# io-board-e-4.net
KiCad netlist of a schematic drawn in EAGLE
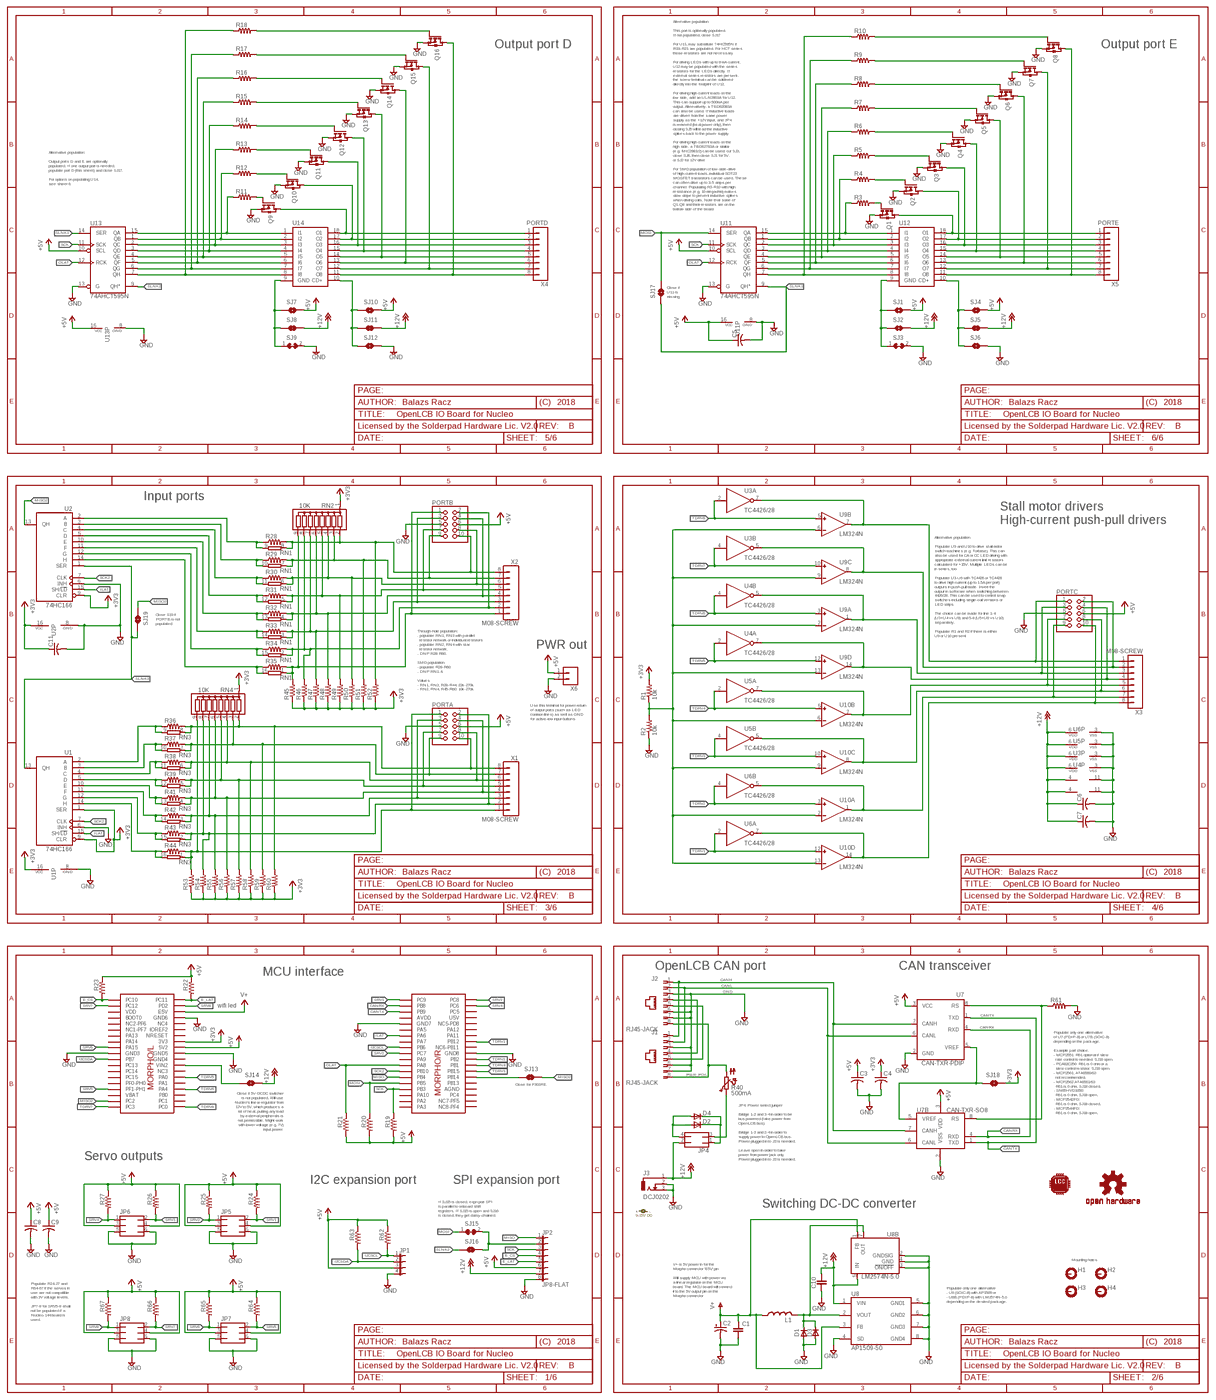
[diagram p0: schematic, sheet 1, overview]
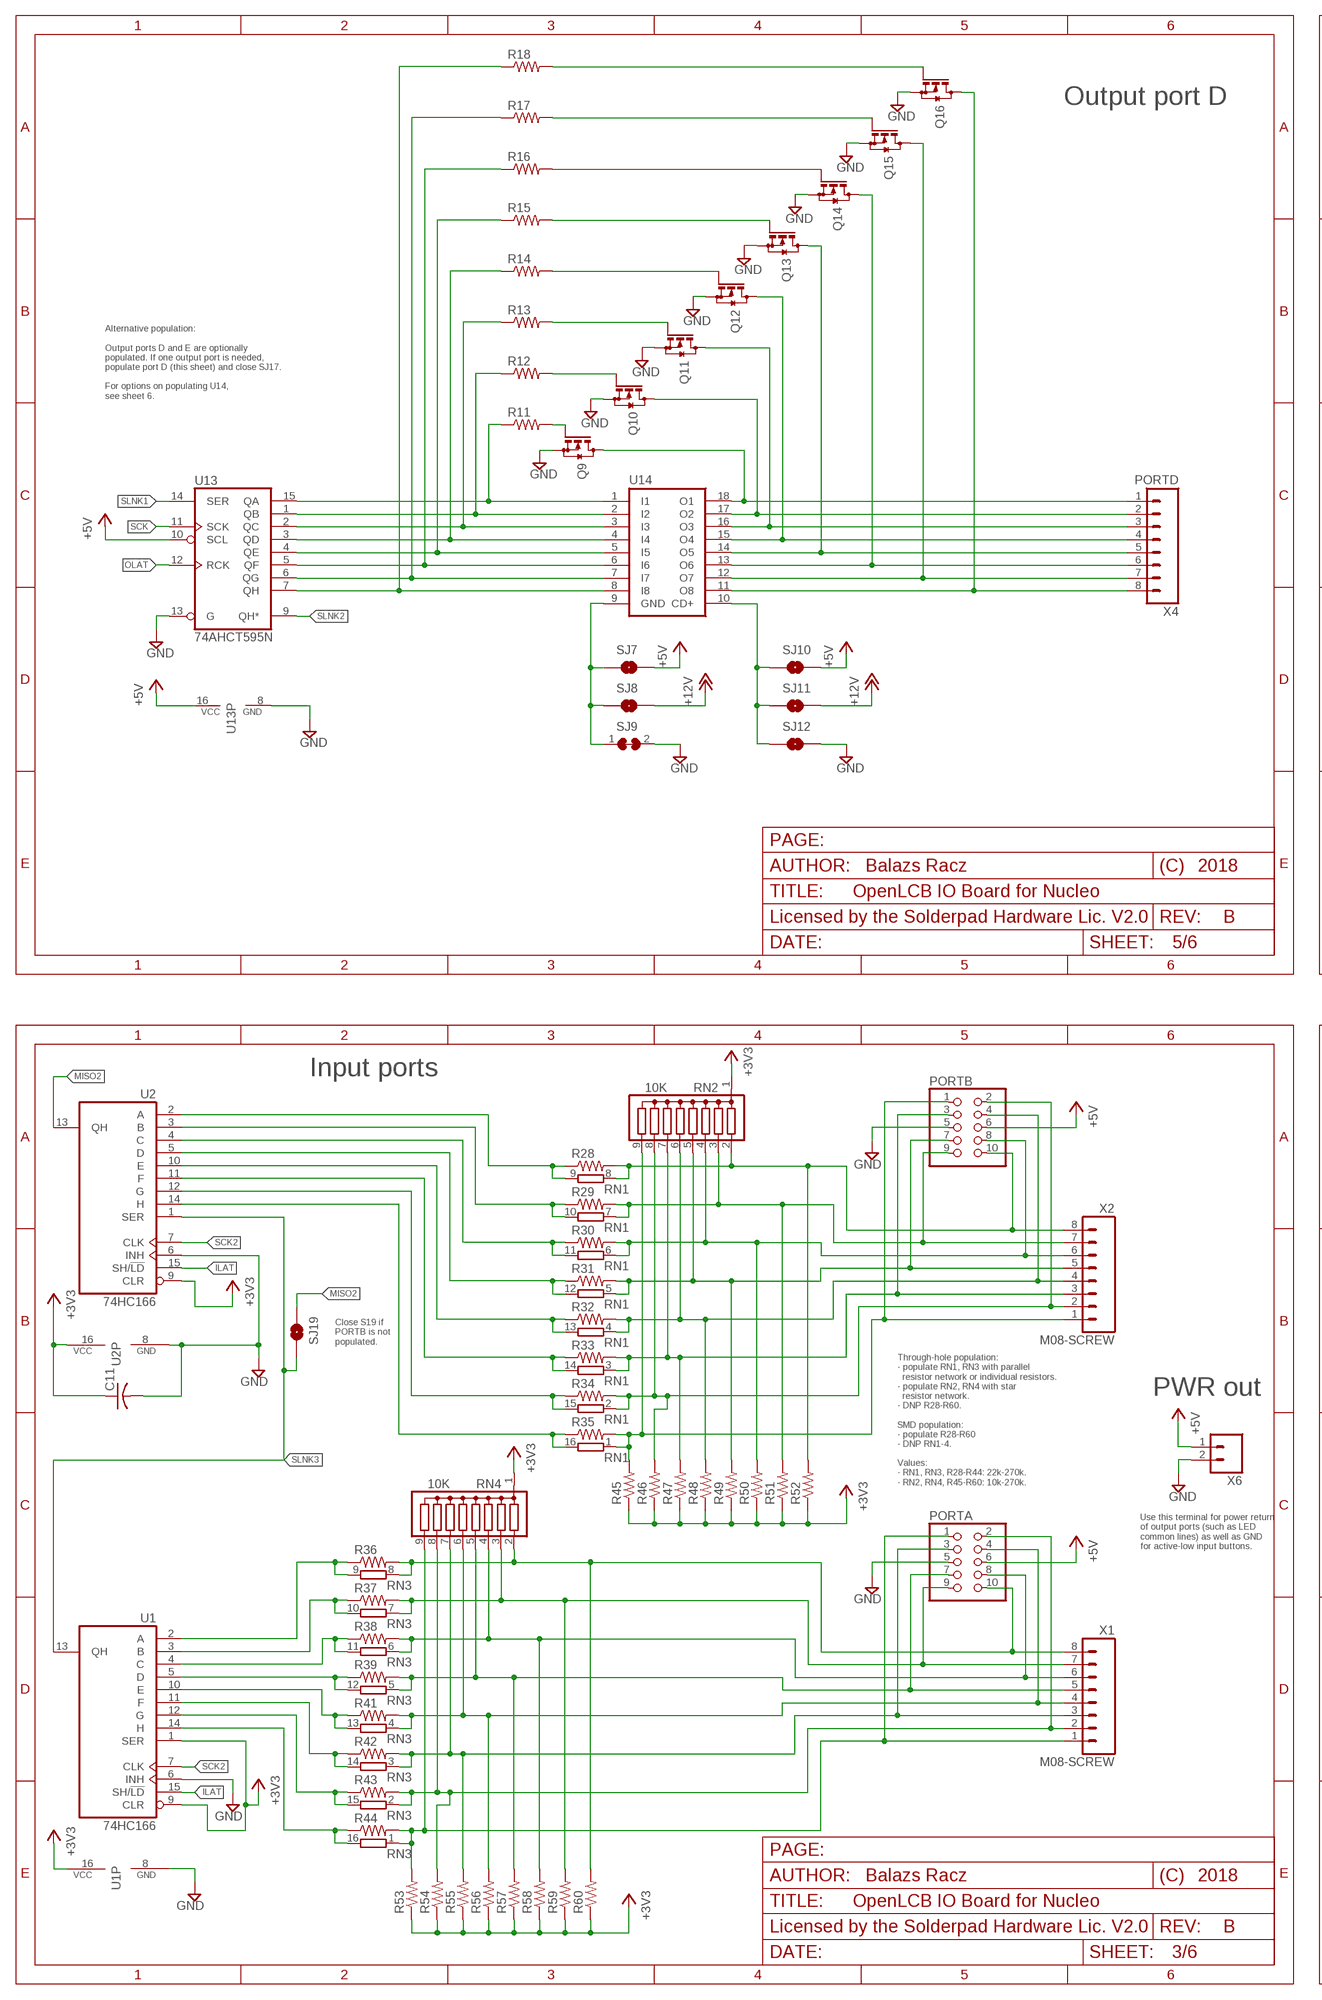
[diagram p1: schematic, sheet 1, part 1 of 4]
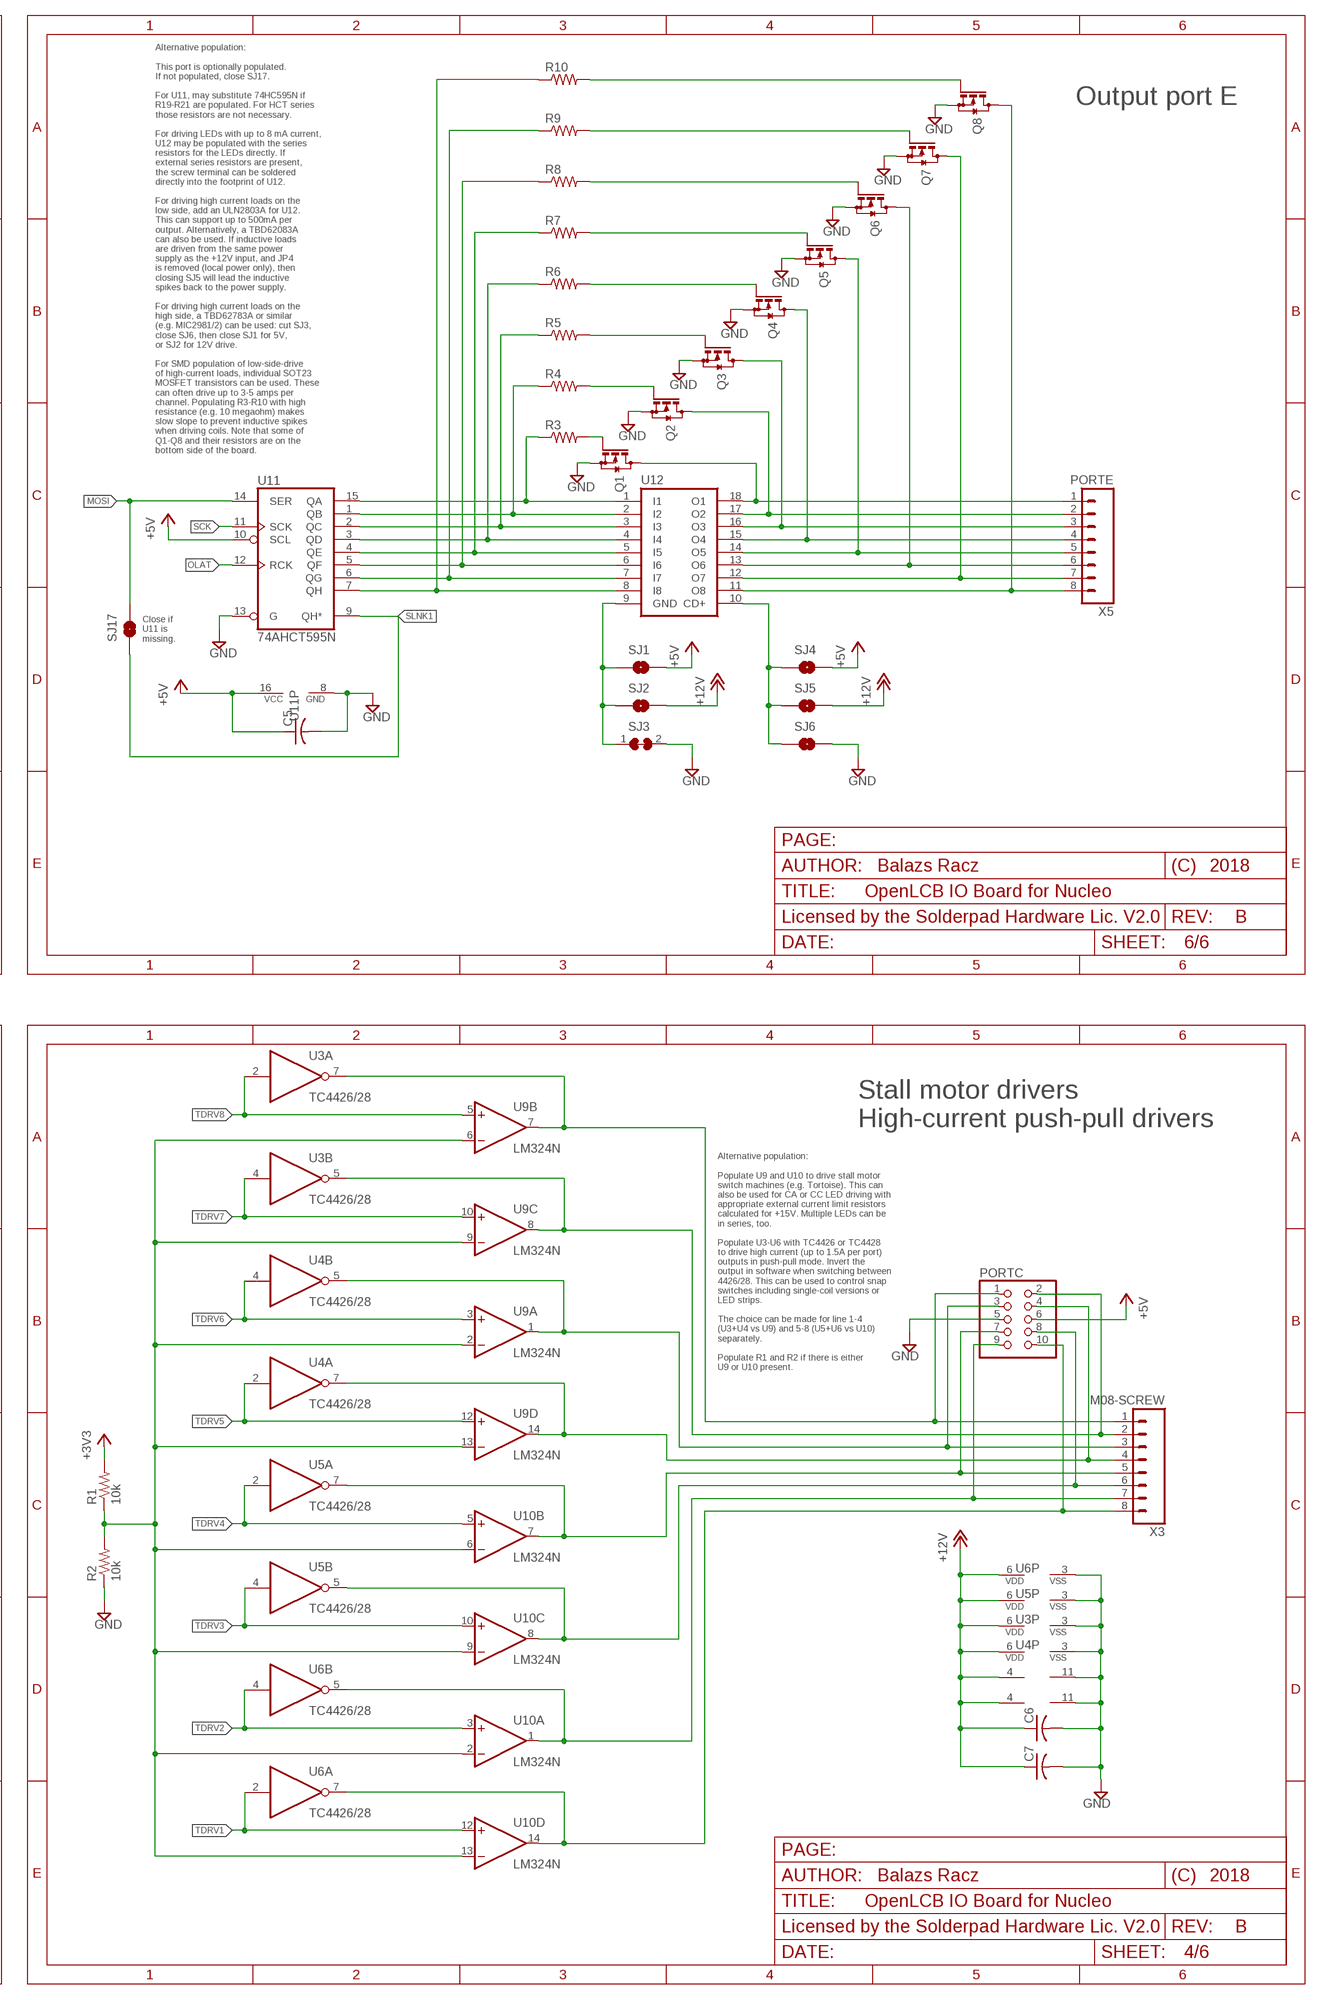
[diagram p2: schematic, sheet 1, part 2 of 4]
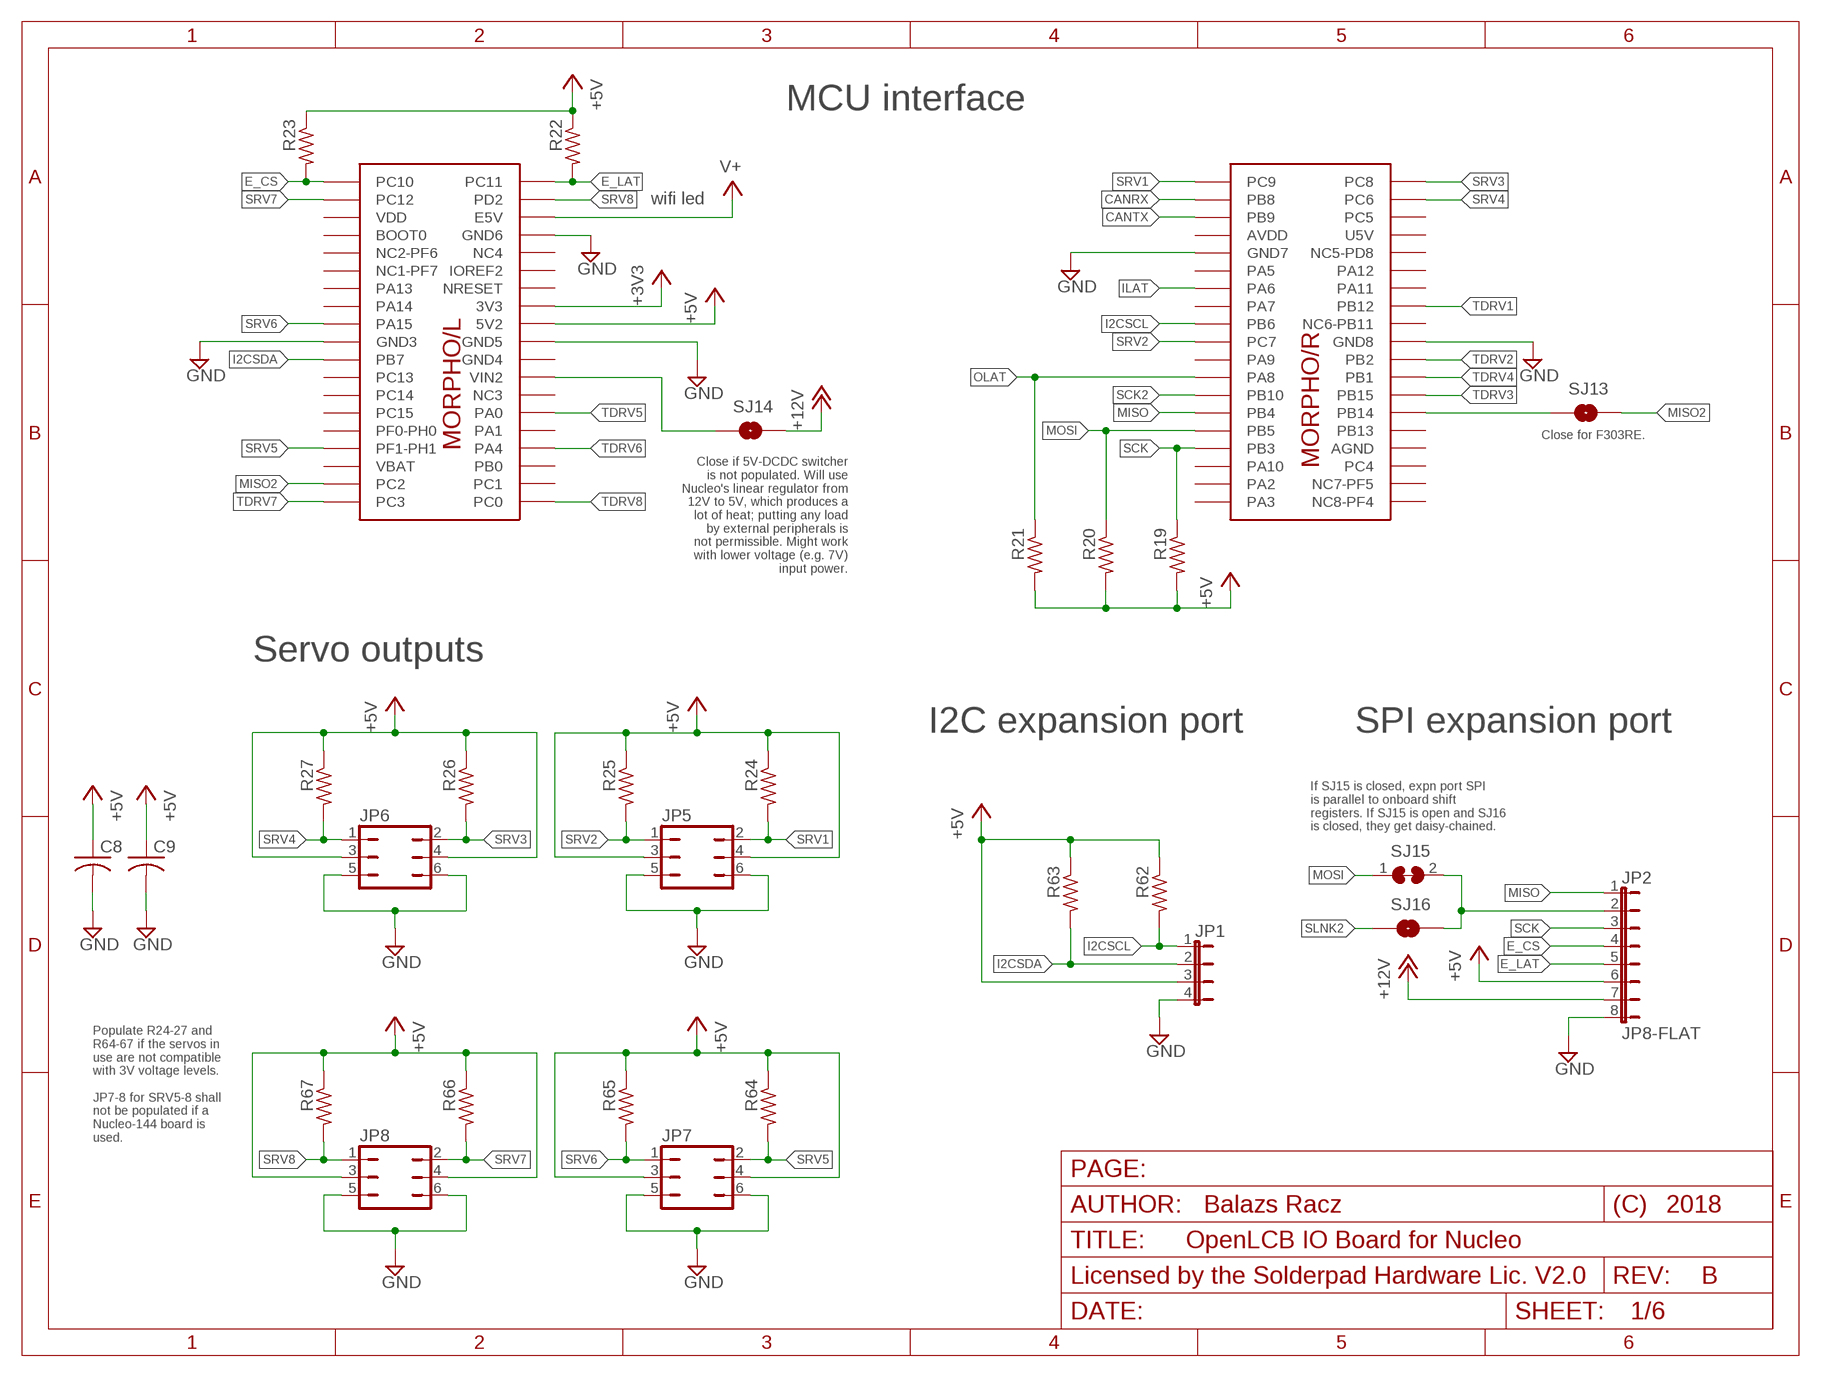
[diagram p3: schematic, sheet 1, part 3 of 4]
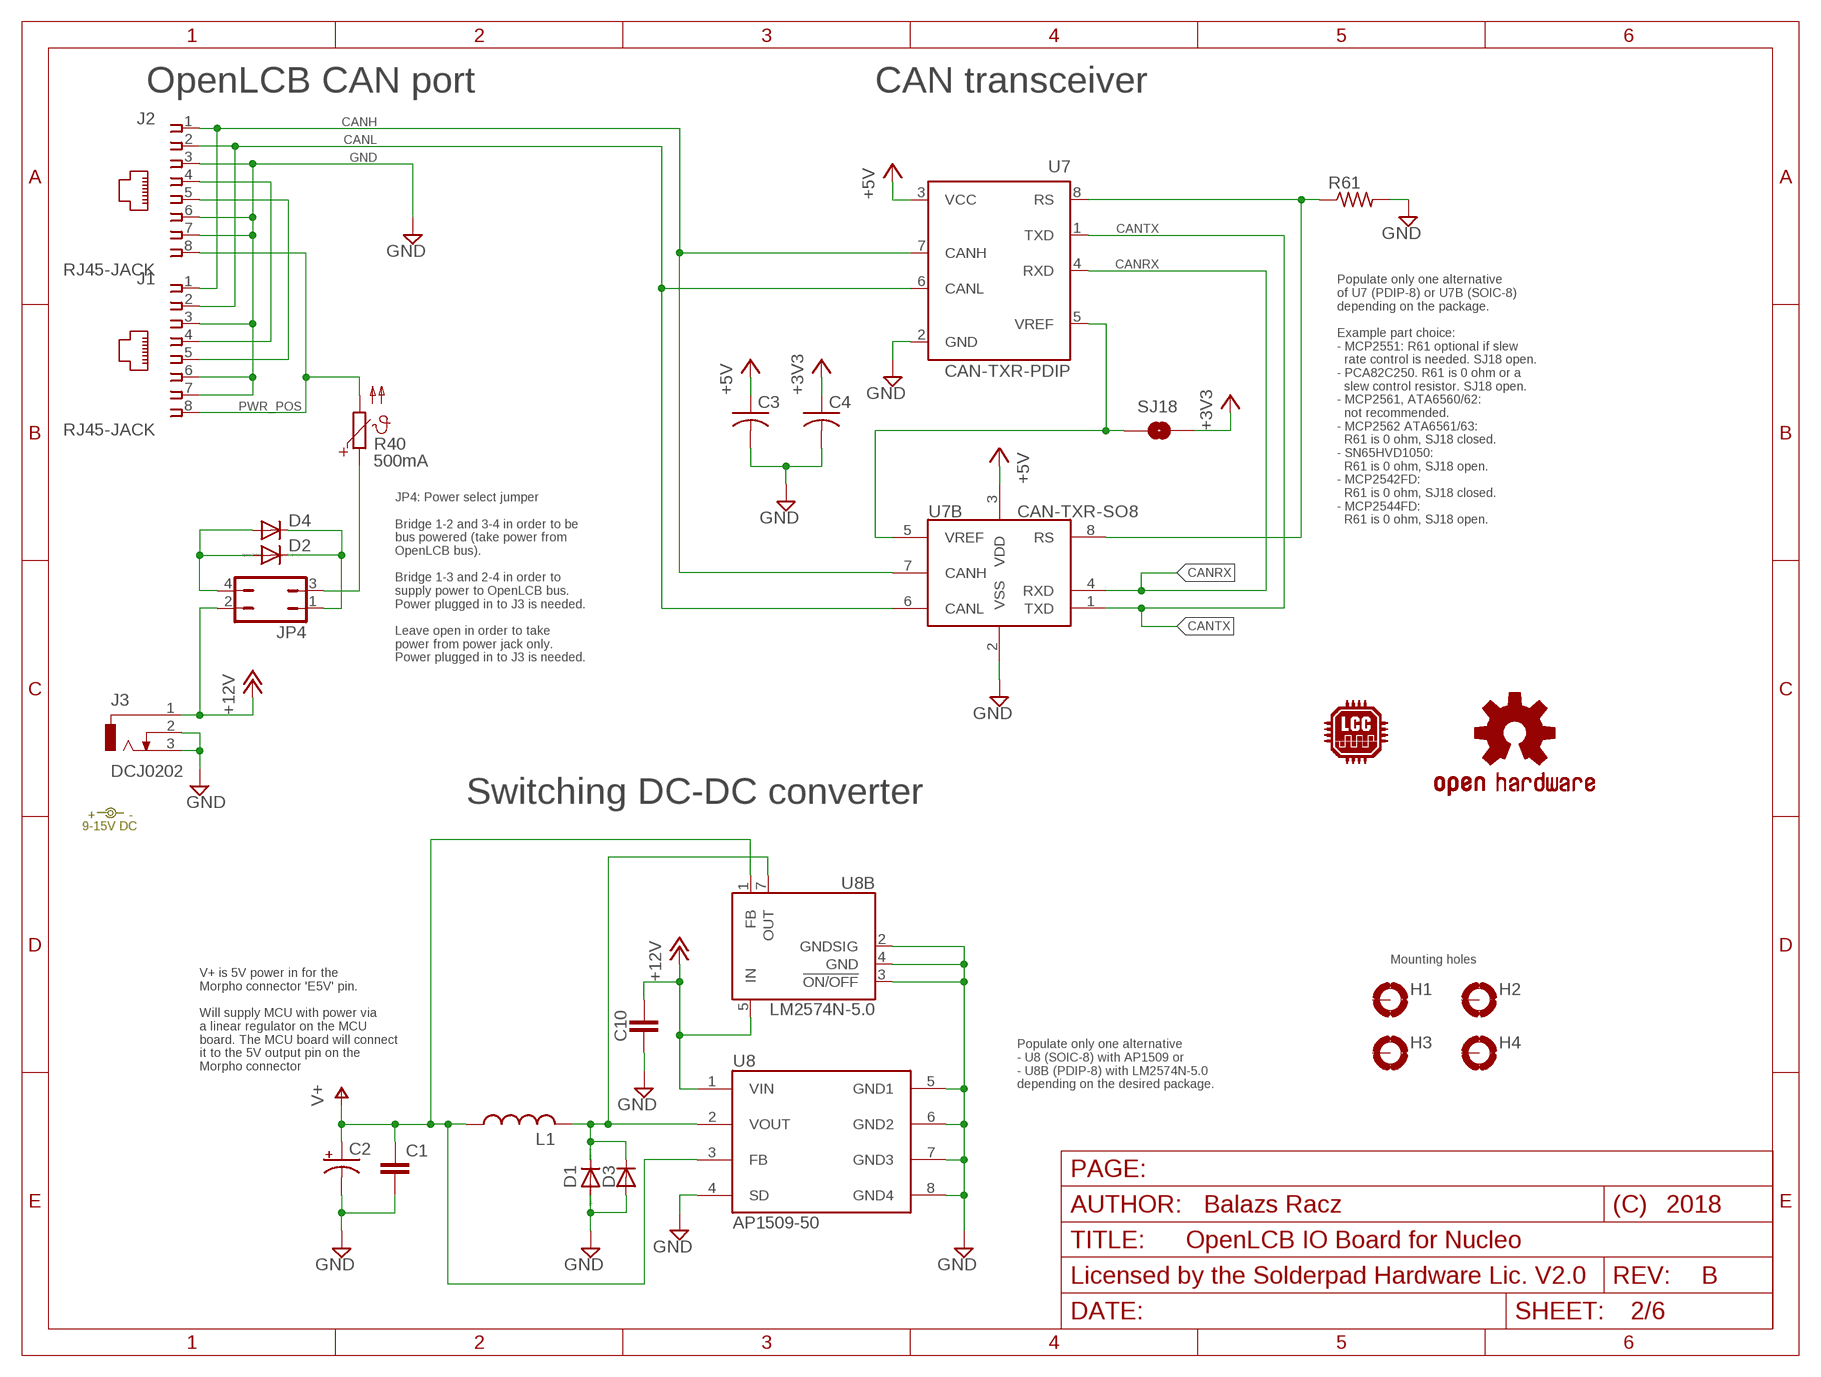
[diagram p4: schematic, sheet 1, part 4 of 4]

(export (version "E")
  (design (tool "Eeschema 10.0.6"))
  (components
    (comp (ref "+12V")
      (value "9-15V DC")
      (footprint "eagle-import:POWER_USAGE")
      (libsource (lib "eagle-import") (part "DOC-POWER_LABEL"))
    )
    (comp (ref "C1")
      (value "C-EUC1206")
      (footprint "eagle-import:C1206")
      (libsource (lib "eagle-import") (part "C-EUC1206"))
    )
    (comp (ref "C2")
      (value "CPOL-USE2.5-5")
      (footprint "eagle-import:E2,5-5")
      (libsource (lib "eagle-import") (part "CPOL-USE2.5-5"))
    )
    (comp (ref "C3")
      (value "C-USC0805")
      (footprint "eagle-import:C0805")
      (libsource (lib "eagle-import") (part "C-USC0805"))
    )
    (comp (ref "C4")
      (value "C-USC0805")
      (footprint "eagle-import:C0805")
      (libsource (lib "eagle-import") (part "C-USC0805"))
    )
    (comp (ref "C5")
      (value "C-USC0805")
      (footprint "eagle-import:C0805")
      (libsource (lib "eagle-import") (part "C-USC0805"))
    )
    (comp (ref "C6")
      (value "C-USC1206")
      (footprint "eagle-import:C1206")
      (libsource (lib "eagle-import") (part "C-USC1206"))
    )
    (comp (ref "C7")
      (value "C-USC1206")
      (footprint "eagle-import:C1206")
      (libsource (lib "eagle-import") (part "C-USC1206"))
    )
    (comp (ref "C8")
      (value "C-USC1206")
      (footprint "eagle-import:C1206")
      (libsource (lib "eagle-import") (part "C-USC1206"))
    )
    (comp (ref "C9")
      (value "C-USC1206")
      (footprint "eagle-import:C1206")
      (libsource (lib "eagle-import") (part "C-USC1206"))
    )
    (comp (ref "C10")
      (value "C-EUC1206")
      (footprint "eagle-import:C1206")
      (libsource (lib "eagle-import") (part "C-EUC1206"))
    )
    (comp (ref "C11")
      (value "C-USC0805")
      (footprint "eagle-import:C0805")
      (libsource (lib "eagle-import") (part "C-USC0805"))
    )
    (comp (ref "D1")
      (value "DIODE-DO41-7.6")
      (footprint "eagle-import:DO41-7.6")
      (libsource (lib "eagle-import") (part "DIODE-DO41-7.6"))
    )
    (comp (ref "D2")
      (value "DIODE-DO41-7.6")
      (footprint "eagle-import:DO41-7.6")
      (libsource (lib "eagle-import") (part "DIODE-DO41-7.6"))
    )
    (comp (ref "D3")
      (value "DIODEDO-214AA-NODOC")
      (footprint "eagle-import:DO214AA-NODOC")
      (libsource (lib "eagle-import") (part "DIODEDO-214AA-NODOC"))
    )
    (comp (ref "D4")
      (value "DIODEDO-214AA-NODOC")
      (footprint "eagle-import:DO214AA-NODOC")
      (libsource (lib "eagle-import") (part "DIODEDO-214AA-NODOC"))
    )
    (comp (ref "H1")
      (value "MOUNT-PAD-ROUND3.3")
      (footprint "eagle-import:3,3-PAD")
      (libsource (lib "eagle-import") (part "MOUNT-PAD-ROUND3.3"))
    )
    (comp (ref "H2")
      (value "MOUNT-PAD-ROUND3.3")
      (footprint "eagle-import:3,3-PAD")
      (libsource (lib "eagle-import") (part "MOUNT-PAD-ROUND3.3"))
    )
    (comp (ref "H3")
      (value "MOUNT-PAD-ROUND3.3")
      (footprint "eagle-import:3,3-PAD")
      (libsource (lib "eagle-import") (part "MOUNT-PAD-ROUND3.3"))
    )
    (comp (ref "H4")
      (value "MOUNT-PAD-ROUND3.3")
      (footprint "eagle-import:3,3-PAD")
      (libsource (lib "eagle-import") (part "MOUNT-PAD-ROUND3.3"))
    )
    (comp (ref "J1")
      (value "RJ45-JACK")
      (footprint "eagle-import:RJ45-PULSE-E5J88")
      (libsource (lib "eagle-import") (part "RJ45-JACKRJ45-PULSE-E5J00"))
    )
    (comp (ref "J2")
      (value "RJ45-JACK")
      (footprint "eagle-import:RJ45-PULSE-E5J88")
      (libsource (lib "eagle-import") (part "RJ45-JACKRJ45-PULSE-E5J00"))
    )
    (comp (ref "J3")
      (value "DCJ0202")
      (footprint "eagle-import:DCJ0202")
      (libsource (lib "eagle-import") (part "DCJ0202"))
    )
    (comp (ref "JP1")
      (value "JP4-FLAT")
      (footprint "eagle-import:JP4F")
      (libsource (lib "eagle-import") (part "JP4-FLAT"))
    )
    (comp (ref "JP2")
      (value "JP8-FLAT")
      (footprint "eagle-import:JP8F")
      (libsource (lib "eagle-import") (part "JP8-FLAT"))
    )
    (comp (ref "JP4")
      (value "JP2Q")
      (footprint "eagle-import:JP2Q")
      (libsource (lib "eagle-import") (part "JP2Q"))
    )
    (comp (ref "JP5")
      (value "JP3Q")
      (footprint "eagle-import:JP3Q")
      (libsource (lib "eagle-import") (part "JP3Q"))
    )
    (comp (ref "JP6")
      (value "JP3Q")
      (footprint "eagle-import:JP3Q")
      (libsource (lib "eagle-import") (part "JP3Q"))
    )
    (comp (ref "JP7")
      (value "JP3Q")
      (footprint "eagle-import:JP3Q")
      (libsource (lib "eagle-import") (part "JP3Q"))
    )
    (comp (ref "JP8")
      (value "JP3Q")
      (footprint "eagle-import:JP3Q")
      (libsource (lib "eagle-import") (part "JP3Q"))
    )
    (comp (ref "L1")
      (value "L-US")
      (footprint "eagle-import:L5-8,5")
      (libsource (lib "eagle-import") (part "L-US"))
    )
    (comp (ref "LG1")
      (value "LCC_LOGO")
      (footprint "eagle-import:LCC_LOGO")
      (libsource (lib "eagle-import") (part "LCC_LOGO"))
    )
    (comp (ref "LOGO1")
      (value "DOC-OSHW-LOGOM")
      (footprint "eagle-import:OSHW-LOGO-M")
      (libsource (lib "eagle-import") (part "DOC-OSHW-LOGOM"))
    )
    (comp (ref "PORTA")
      (value "PINHD-2X5CN")
      (footprint "eagle-import:CON10M")
      (libsource (lib "eagle-import") (part "PINHD-2X5CN"))
    )
    (comp (ref "PORTB")
      (value "PINHD-2X5CN")
      (footprint "eagle-import:CON10M")
      (libsource (lib "eagle-import") (part "PINHD-2X5CN"))
    )
    (comp (ref "PORTC")
      (value "PINHD-2X5CN")
      (footprint "eagle-import:CON10M")
      (libsource (lib "eagle-import") (part "PINHD-2X5CN"))
    )
    (comp (ref "Q1")
      (value "BSS123")
      (footprint "eagle-import:SOT23")
      (libsource (lib "eagle-import") (part "BSS123"))
    )
    (comp (ref "Q2")
      (value "BSS123")
      (footprint "eagle-import:SOT23")
      (libsource (lib "eagle-import") (part "BSS123"))
    )
    (comp (ref "Q3")
      (value "BSS123")
      (footprint "eagle-import:SOT23")
      (libsource (lib "eagle-import") (part "BSS123"))
    )
    (comp (ref "Q4")
      (value "BSS123")
      (footprint "eagle-import:SOT23")
      (libsource (lib "eagle-import") (part "BSS123"))
    )
    (comp (ref "Q5")
      (value "BSS123")
      (footprint "eagle-import:SOT23")
      (libsource (lib "eagle-import") (part "BSS123"))
    )
    (comp (ref "Q6")
      (value "BSS123")
      (footprint "eagle-import:SOT23")
      (libsource (lib "eagle-import") (part "BSS123"))
    )
    (comp (ref "Q7")
      (value "BSS123")
      (footprint "eagle-import:SOT23")
      (libsource (lib "eagle-import") (part "BSS123"))
    )
    (comp (ref "Q8")
      (value "BSS123")
      (footprint "eagle-import:SOT23")
      (libsource (lib "eagle-import") (part "BSS123"))
    )
    (comp (ref "Q9")
      (value "BSS123")
      (footprint "eagle-import:SOT23")
      (libsource (lib "eagle-import") (part "BSS123"))
    )
    (comp (ref "Q10")
      (value "BSS123")
      (footprint "eagle-import:SOT23")
      (libsource (lib "eagle-import") (part "BSS123"))
    )
    (comp (ref "Q11")
      (value "BSS123")
      (footprint "eagle-import:SOT23")
      (libsource (lib "eagle-import") (part "BSS123"))
    )
    (comp (ref "Q12")
      (value "BSS123")
      (footprint "eagle-import:SOT23")
      (libsource (lib "eagle-import") (part "BSS123"))
    )
    (comp (ref "Q13")
      (value "BSS123")
      (footprint "eagle-import:SOT23")
      (libsource (lib "eagle-import") (part "BSS123"))
    )
    (comp (ref "Q14")
      (value "BSS123")
      (footprint "eagle-import:SOT23")
      (libsource (lib "eagle-import") (part "BSS123"))
    )
    (comp (ref "Q15")
      (value "BSS123")
      (footprint "eagle-import:SOT23")
      (libsource (lib "eagle-import") (part "BSS123"))
    )
    (comp (ref "Q16")
      (value "BSS123")
      (footprint "eagle-import:SOT23")
      (libsource (lib "eagle-import") (part "BSS123"))
    )
    (comp (ref "R1")
      (value "10k")
      (footprint "eagle-import:R0805")
      (libsource (lib "eagle-import") (part "R-US_R0805"))
    )
    (comp (ref "R2")
      (value "10k")
      (footprint "eagle-import:R0805")
      (libsource (lib "eagle-import") (part "R-US_R0805"))
    )
    (comp (ref "R3")
      (value "R-US_R0603")
      (footprint "eagle-import:R0603")
      (libsource (lib "eagle-import") (part "R-US_R0603"))
    )
    (comp (ref "R4")
      (value "R-US_R0603")
      (footprint "eagle-import:R0603")
      (libsource (lib "eagle-import") (part "R-US_R0603"))
    )
    (comp (ref "R5")
      (value "R-US_R0603")
      (footprint "eagle-import:R0603")
      (libsource (lib "eagle-import") (part "R-US_R0603"))
    )
    (comp (ref "R6")
      (value "R-US_R0603")
      (footprint "eagle-import:R0603")
      (libsource (lib "eagle-import") (part "R-US_R0603"))
    )
    (comp (ref "R7")
      (value "R-US_R0603")
      (footprint "eagle-import:R0603")
      (libsource (lib "eagle-import") (part "R-US_R0603"))
    )
    (comp (ref "R8")
      (value "R-US_R0603")
      (footprint "eagle-import:R0603")
      (libsource (lib "eagle-import") (part "R-US_R0603"))
    )
    (comp (ref "R9")
      (value "R-US_R0603")
      (footprint "eagle-import:R0603")
      (libsource (lib "eagle-import") (part "R-US_R0603"))
    )
    (comp (ref "R10")
      (value "R-US_R0603")
      (footprint "eagle-import:R0603")
      (libsource (lib "eagle-import") (part "R-US_R0603"))
    )
    (comp (ref "R11")
      (value "R-US_R0603")
      (footprint "eagle-import:R0603")
      (libsource (lib "eagle-import") (part "R-US_R0603"))
    )
    (comp (ref "R12")
      (value "R-US_R0603")
      (footprint "eagle-import:R0603")
      (libsource (lib "eagle-import") (part "R-US_R0603"))
    )
    (comp (ref "R13")
      (value "R-US_R0603")
      (footprint "eagle-import:R0603")
      (libsource (lib "eagle-import") (part "R-US_R0603"))
    )
    (comp (ref "R14")
      (value "R-US_R0603")
      (footprint "eagle-import:R0603")
      (libsource (lib "eagle-import") (part "R-US_R0603"))
    )
    (comp (ref "R15")
      (value "R-US_R0603")
      (footprint "eagle-import:R0603")
      (libsource (lib "eagle-import") (part "R-US_R0603"))
    )
    (comp (ref "R16")
      (value "R-US_R0603")
      (footprint "eagle-import:R0603")
      (libsource (lib "eagle-import") (part "R-US_R0603"))
    )
    (comp (ref "R17")
      (value "R-US_R0603")
      (footprint "eagle-import:R0603")
      (libsource (lib "eagle-import") (part "R-US_R0603"))
    )
    (comp (ref "R18")
      (value "R-US_R0603")
      (footprint "eagle-import:R0603")
      (libsource (lib "eagle-import") (part "R-US_R0603"))
    )
    (comp (ref "R19")
      (value "R-US_R0805")
      (footprint "eagle-import:R0805")
      (libsource (lib "eagle-import") (part "rcl_334_R-US_R0805"))
    )
    (comp (ref "R20")
      (value "R-US_R0805")
      (footprint "eagle-import:R0805")
      (libsource (lib "eagle-import") (part "rcl_334_R-US_R0805"))
    )
    (comp (ref "R21")
      (value "R-US_R0805")
      (footprint "eagle-import:R0805")
      (libsource (lib "eagle-import") (part "rcl_334_R-US_R0805"))
    )
    (comp (ref "R22")
      (value "R-US_R0805")
      (footprint "eagle-import:R0805")
      (libsource (lib "eagle-import") (part "rcl_334_R-US_R0805"))
    )
    (comp (ref "R23")
      (value "R-US_R0805")
      (footprint "eagle-import:R0805")
      (libsource (lib "eagle-import") (part "rcl_334_R-US_R0805"))
    )
    (comp (ref "R24")
      (value "R-US_R0805")
      (footprint "eagle-import:R0805")
      (libsource (lib "eagle-import") (part "rcl_334_R-US_R0805"))
    )
    (comp (ref "R25")
      (value "R-US_R0805")
      (footprint "eagle-import:R0805")
      (libsource (lib "eagle-import") (part "rcl_334_R-US_R0805"))
    )
    (comp (ref "R26")
      (value "R-US_R0805")
      (footprint "eagle-import:R0805")
      (libsource (lib "eagle-import") (part "rcl_334_R-US_R0805"))
    )
    (comp (ref "R27")
      (value "R-US_R0805")
      (footprint "eagle-import:R0805")
      (libsource (lib "eagle-import") (part "rcl_334_R-US_R0805"))
    )
    (comp (ref "R28")
      (value "R-US_R0603")
      (footprint "eagle-import:R0603")
      (libsource (lib "eagle-import") (part "rcl_334_R-US_R0603"))
    )
    (comp (ref "R29")
      (value "R-US_R0603")
      (footprint "eagle-import:R0603")
      (libsource (lib "eagle-import") (part "rcl_334_R-US_R0603"))
    )
    (comp (ref "R30")
      (value "R-US_R0603")
      (footprint "eagle-import:R0603")
      (libsource (lib "eagle-import") (part "rcl_334_R-US_R0603"))
    )
    (comp (ref "R31")
      (value "R-US_R0603")
      (footprint "eagle-import:R0603")
      (libsource (lib "eagle-import") (part "rcl_334_R-US_R0603"))
    )
    (comp (ref "R32")
      (value "R-US_R0603")
      (footprint "eagle-import:R0603")
      (libsource (lib "eagle-import") (part "rcl_334_R-US_R0603"))
    )
    (comp (ref "R33")
      (value "R-US_R0603")
      (footprint "eagle-import:R0603")
      (libsource (lib "eagle-import") (part "rcl_334_R-US_R0603"))
    )
    (comp (ref "R34")
      (value "R-US_R0603")
      (footprint "eagle-import:R0603")
      (libsource (lib "eagle-import") (part "rcl_334_R-US_R0603"))
    )
    (comp (ref "R35")
      (value "R-US_R0603")
      (footprint "eagle-import:R0603")
      (libsource (lib "eagle-import") (part "rcl_334_R-US_R0603"))
    )
    (comp (ref "R36")
      (value "R-US_R0603")
      (footprint "eagle-import:R0603")
      (libsource (lib "eagle-import") (part "rcl_334_R-US_R0603"))
    )
    (comp (ref "R37")
      (value "R-US_R0603")
      (footprint "eagle-import:R0603")
      (libsource (lib "eagle-import") (part "rcl_334_R-US_R0603"))
    )
    (comp (ref "R38")
      (value "R-US_R0603")
      (footprint "eagle-import:R0603")
      (libsource (lib "eagle-import") (part "rcl_334_R-US_R0603"))
    )
    (comp (ref "R39")
      (value "R-US_R0603")
      (footprint "eagle-import:R0603")
      (libsource (lib "eagle-import") (part "rcl_334_R-US_R0603"))
    )
    (comp (ref "R40")
      (value "500mA")
      (footprint "eagle-import:PTC1812")
      (libsource (lib "eagle-import") (part "PTC_1812"))
    )
    (comp (ref "R41")
      (value "R-US_R0603")
      (footprint "eagle-import:R0603")
      (libsource (lib "eagle-import") (part "rcl_334_R-US_R0603"))
    )
    (comp (ref "R42")
      (value "R-US_R0603")
      (footprint "eagle-import:R0603")
      (libsource (lib "eagle-import") (part "rcl_334_R-US_R0603"))
    )
    (comp (ref "R43")
      (value "R-US_R0603")
      (footprint "eagle-import:R0603")
      (libsource (lib "eagle-import") (part "rcl_334_R-US_R0603"))
    )
    (comp (ref "R44")
      (value "R-US_R0603")
      (footprint "eagle-import:R0603")
      (libsource (lib "eagle-import") (part "rcl_334_R-US_R0603"))
    )
    (comp (ref "R45")
      (value "R-US")
      (footprint "eagle-import:R0603")
      (libsource (lib "eagle-import") (part "R-US"))
    )
    (comp (ref "R46")
      (value "R-US")
      (footprint "eagle-import:R0603")
      (libsource (lib "eagle-import") (part "R-US"))
    )
    (comp (ref "R47")
      (value "R-US")
      (footprint "eagle-import:R0603")
      (libsource (lib "eagle-import") (part "R-US"))
    )
    (comp (ref "R48")
      (value "R-US")
      (footprint "eagle-import:R0603")
      (libsource (lib "eagle-import") (part "R-US"))
    )
    (comp (ref "R49")
      (value "R-US")
      (footprint "eagle-import:R0603")
      (libsource (lib "eagle-import") (part "R-US"))
    )
    (comp (ref "R50")
      (value "R-US")
      (footprint "eagle-import:R0603")
      (libsource (lib "eagle-import") (part "R-US"))
    )
    (comp (ref "R51")
      (value "R-US")
      (footprint "eagle-import:R0603")
      (libsource (lib "eagle-import") (part "R-US"))
    )
    (comp (ref "R52")
      (value "R-US")
      (footprint "eagle-import:R0603")
      (libsource (lib "eagle-import") (part "R-US"))
    )
    (comp (ref "R53")
      (value "R-US")
      (footprint "eagle-import:R0603")
      (libsource (lib "eagle-import") (part "R-US"))
    )
    (comp (ref "R54")
      (value "R-US")
      (footprint "eagle-import:R0603")
      (libsource (lib "eagle-import") (part "R-US"))
    )
    (comp (ref "R55")
      (value "R-US")
      (footprint "eagle-import:R0603")
      (libsource (lib "eagle-import") (part "R-US"))
    )
    (comp (ref "R56")
      (value "R-US")
      (footprint "eagle-import:R0603")
      (libsource (lib "eagle-import") (part "R-US"))
    )
    (comp (ref "R57")
      (value "R-US")
      (footprint "eagle-import:R0603")
      (libsource (lib "eagle-import") (part "R-US"))
    )
    (comp (ref "R58")
      (value "R-US")
      (footprint "eagle-import:R0603")
      (libsource (lib "eagle-import") (part "R-US"))
    )
    (comp (ref "R59")
      (value "R-US")
      (footprint "eagle-import:R0603")
      (libsource (lib "eagle-import") (part "R-US"))
    )
    (comp (ref "R60")
      (value "R-US")
      (footprint "eagle-import:R0603")
      (libsource (lib "eagle-import") (part "R-US"))
    )
    (comp (ref "R61")
      (value "R-US_R0805")
      (footprint "eagle-import:R0805")
      (libsource (lib "eagle-import") (part "rcl_334_R-US_R0805"))
    )
    (comp (ref "R62")
      (value "R-US_R0805")
      (footprint "eagle-import:R0805")
      (libsource (lib "eagle-import") (part "rcl_334_R-US_R0805"))
    )
    (comp (ref "R63")
      (value "R-US_R0805")
      (footprint "eagle-import:R0805")
      (libsource (lib "eagle-import") (part "rcl_334_R-US_R0805"))
    )
    (comp (ref "R64")
      (value "R-US_R0805")
      (footprint "eagle-import:R0805")
      (libsource (lib "eagle-import") (part "rcl_334_R-US_R0805"))
    )
    (comp (ref "R65")
      (value "R-US_R0805")
      (footprint "eagle-import:R0805")
      (libsource (lib "eagle-import") (part "rcl_334_R-US_R0805"))
    )
    (comp (ref "R66")
      (value "R-US_R0805")
      (footprint "eagle-import:R0805")
      (libsource (lib "eagle-import") (part "rcl_334_R-US_R0805"))
    )
    (comp (ref "R67")
      (value "R-US_R0805")
      (footprint "eagle-import:R0805")
      (libsource (lib "eagle-import") (part "rcl_334_R-US_R0805"))
    )
    (comp (ref "RN1")
      (value "8R-P")
      (footprint "eagle-import:DIL16")
      (libsource (lib "eagle-import") (part "8R-P"))
    )
    (comp (ref "RN2")
      (value "10K")
      (footprint "eagle-import:SIL9")
      (libsource (lib "eagle-import") (part "G08R"))
    )
    (comp (ref "RN3")
      (value "8R-P")
      (footprint "eagle-import:DIL16")
      (libsource (lib "eagle-import") (part "8R-P"))
    )
    (comp (ref "RN4")
      (value "10K")
      (footprint "eagle-import:SIL9")
      (libsource (lib "eagle-import") (part "G08R"))
    )
    (comp (ref "SJ1")
      (value "SJRND2")
      (footprint "eagle-import:SJ_RND2")
      (libsource (lib "eagle-import") (part "SJRND2"))
    )
    (comp (ref "SJ2")
      (value "SJRND2")
      (footprint "eagle-import:SJ_RND2")
      (libsource (lib "eagle-import") (part "SJRND2"))
    )
    (comp (ref "SJ3")
      (value "SJ-C")
      (footprint "eagle-import:SJW-C")
      (libsource (lib "eagle-import") (part "SJ-C"))
    )
    (comp (ref "SJ4")
      (value "SJRND2")
      (footprint "eagle-import:SJ_RND2")
      (libsource (lib "eagle-import") (part "SJRND2"))
    )
    (comp (ref "SJ5")
      (value "SJRND2")
      (footprint "eagle-import:SJ_RND2")
      (libsource (lib "eagle-import") (part "SJRND2"))
    )
    (comp (ref "SJ6")
      (value "SJRND2")
      (footprint "eagle-import:SJ_RND2")
      (libsource (lib "eagle-import") (part "SJRND2"))
    )
    (comp (ref "SJ7")
      (value "SJRND2")
      (footprint "eagle-import:SJ_RND2")
      (libsource (lib "eagle-import") (part "SJRND2"))
    )
    (comp (ref "SJ8")
      (value "SJRND2")
      (footprint "eagle-import:SJ_RND2")
      (libsource (lib "eagle-import") (part "SJRND2"))
    )
    (comp (ref "SJ9")
      (value "SJ-C")
      (footprint "eagle-import:SJW-C")
      (libsource (lib "eagle-import") (part "SJ-C"))
    )
    (comp (ref "SJ10")
      (value "SJRND2")
      (footprint "eagle-import:SJ_RND2")
      (libsource (lib "eagle-import") (part "SJRND2"))
    )
    (comp (ref "SJ11")
      (value "SJRND2")
      (footprint "eagle-import:SJ_RND2")
      (libsource (lib "eagle-import") (part "SJRND2"))
    )
    (comp (ref "SJ12")
      (value "SJRND2")
      (footprint "eagle-import:SJ_RND2")
      (libsource (lib "eagle-import") (part "SJRND2"))
    )
    (comp (ref "SJ13")
      (value "SJRND2")
      (footprint "eagle-import:SJ_RND2")
      (libsource (lib "eagle-import") (part "SJRND2"))
    )
    (comp (ref "SJ14")
      (value "SJRND2")
      (footprint "eagle-import:SJ_RND2")
      (libsource (lib "eagle-import") (part "SJRND2"))
    )
    (comp (ref "SJ15")
      (value "SJ-C")
      (footprint "eagle-import:SJW-C")
      (libsource (lib "eagle-import") (part "SJ-C"))
    )
    (comp (ref "SJ16")
      (value "SJRND2")
      (footprint "eagle-import:SJ_RND2")
      (libsource (lib "eagle-import") (part "SJRND2"))
    )
    (comp (ref "SJ17")
      (value "SJRND2")
      (footprint "eagle-import:SJ_RND2")
      (libsource (lib "eagle-import") (part "SJRND2"))
    )
    (comp (ref "SJ18")
      (value "SJRND2")
      (footprint "eagle-import:SJ_RND2")
      (libsource (lib "eagle-import") (part "SJRND2"))
    )
    (comp (ref "SJ19")
      (value "SJRND2")
      (footprint "eagle-import:SJ_RND2")
      (libsource (lib "eagle-import") (part "SJRND2"))
    )
    (comp (ref "U$1")
      (value "NUCLEO_64_GENERIC")
      (footprint "eagle-import:NUCLEO_BRD_BASE64")
      (libsource (lib "eagle-import") (part "NUCLEO_64_GENERIC"))
    )
    (comp (ref "U1")
      (value "74HC166")
      (footprint "eagle-import:DIL16")
      (libsource (lib "eagle-import") (part "74166N"))
    )
    (comp (ref "U2")
      (value "74HC166")
      (footprint "eagle-import:DIL16")
      (libsource (lib "eagle-import") (part "74166N"))
    )
    (comp (ref "U3")
      (value "TC4426/28")
      (footprint "eagle-import:DIL08-LONG")
      (libsource (lib "eagle-import") (part "TC4426APDIP"))
    )
    (comp (ref "U4")
      (value "TC4426/28")
      (footprint "eagle-import:DIL08-LONG")
      (libsource (lib "eagle-import") (part "TC4426APDIP"))
    )
    (comp (ref "U5")
      (value "TC4426/28")
      (footprint "eagle-import:DIL08-LONG")
      (libsource (lib "eagle-import") (part "TC4426APDIP"))
    )
    (comp (ref "U6")
      (value "TC4426/28")
      (footprint "eagle-import:DIL08-LONG")
      (libsource (lib "eagle-import") (part "TC4426APDIP"))
    )
    (comp (ref "U7")
      (value "CAN-TXR-PDIP")
      (footprint "eagle-import:DIL08")
      (libsource (lib "eagle-import") (part "PCA82C250"))
    )
    (comp (ref "U7B")
      (value "CAN-TXR-SO8")
      (footprint "eagle-import:SO-08")
      (libsource (lib "eagle-import") (part "MCP2551-SN"))
    )
    (comp (ref "U8")
      (value "AP1509-50")
      (footprint "eagle-import:SO-08")
      (libsource (lib "eagle-import") (part "AP1509"))
    )
    (comp (ref "U8B")
      (value "LM2574N-5.0")
      (footprint "eagle-import:DIL08")
      (libsource (lib "eagle-import") (part "LM2574?-N5.0"))
    )
    (comp (ref "U9")
      (value "LM324N")
      (footprint "eagle-import:DIL14")
      (libsource (lib "eagle-import") (part "LM324N"))
    )
    (comp (ref "U10")
      (value "LM324N")
      (footprint "eagle-import:DIL14")
      (libsource (lib "eagle-import") (part "LM324N"))
    )
    (comp (ref "U11")
      (value "74AHCT595N")
      (footprint "eagle-import:DIL16")
      (libsource (lib "eagle-import") (part "74595NHCT"))
    )
    (comp (ref "U12")
      (value "ULN2803A")
      (footprint "eagle-import:DIL18-THIN")
      (libsource (lib "eagle-import") (part "ULN2803A"))
    )
    (comp (ref "U13")
      (value "74AHCT595N")
      (footprint "eagle-import:DIL16")
      (libsource (lib "eagle-import") (part "74595NHCT"))
    )
    (comp (ref "U14")
      (value "ULN2803A")
      (footprint "eagle-import:DIL18-THIN")
      (libsource (lib "eagle-import") (part "ULN2803A"))
    )
    (comp (ref "X1")
      (value "M08-SCREW")
      (footprint "eagle-import:1X08_TERMINAL")
      (libsource (lib "eagle-import") (part "M08-SCREW"))
    )
    (comp (ref "X2")
      (value "M08-SCREW")
      (footprint "eagle-import:1X08_TERMINAL")
      (libsource (lib "eagle-import") (part "M08-SCREW"))
    )
    (comp (ref "X3")
      (value "M08-SCREW")
      (footprint "eagle-import:1X08_TERMINAL")
      (libsource (lib "eagle-import") (part "M08-SCREW"))
    )
    (comp (ref "X4")
      (value "PORTD")
      (footprint "eagle-import:1X08_TERMINAL")
      (libsource (lib "eagle-import") (part "M08-SCREW"))
    )
    (comp (ref "X5")
      (value "PORTE")
      (footprint "eagle-import:1X08_TERMINAL")
      (libsource (lib "eagle-import") (part "M08-SCREW"))
    )
    (comp (ref "X6")
      (value "CONNECTOR-M023.5MM-LOCK")
      (footprint "eagle-import:SCREWTERMINAL-3.5MM-2_LOCK")
      (libsource (lib "eagle-import") (part "CONNECTOR-M023.5MM-LOCK"))
    )
  )
  (nets
    (net (code "1") (name "+3V3") (class "Default")
      (node (ref "C11") (pin "1") (pinfunction "1_1") (pintype "passive"))
      (node (ref "C4") (pin "1") (pinfunction "1_1") (pintype "passive"))
      (node (ref "R1") (pin "2") (pinfunction "2_2") (pintype "passive"))
      (node (ref "R45") (pin "1") (pinfunction "1_1") (pintype "passive"))
      (node (ref "R46") (pin "1") (pinfunction "1_1") (pintype "passive"))
      (node (ref "R47") (pin "1") (pinfunction "1_1") (pintype "passive"))
      (node (ref "R48") (pin "1") (pinfunction "1_1") (pintype "passive"))
      (node (ref "R49") (pin "1") (pinfunction "1_1") (pintype "passive"))
      (node (ref "R50") (pin "1") (pinfunction "1_1") (pintype "passive"))
      (node (ref "R51") (pin "1") (pinfunction "1_1") (pintype "passive"))
      (node (ref "R52") (pin "1") (pinfunction "1_1") (pintype "passive"))
      (node (ref "R53") (pin "1") (pinfunction "1_1") (pintype "passive"))
      (node (ref "R54") (pin "1") (pinfunction "1_1") (pintype "passive"))
      (node (ref "R55") (pin "1") (pinfunction "1_1") (pintype "passive"))
      (node (ref "R56") (pin "1") (pinfunction "1_1") (pintype "passive"))
      (node (ref "R57") (pin "1") (pinfunction "1_1") (pintype "passive"))
      (node (ref "R58") (pin "1") (pinfunction "1_1") (pintype "passive"))
      (node (ref "R59") (pin "1") (pinfunction "1_1") (pintype "passive"))
      (node (ref "R60") (pin "1") (pinfunction "1_1") (pintype "passive"))
      (node (ref "RN2") (pin "1") (pinfunction "1_1") (pintype "passive"))
      (node (ref "RN4") (pin "1") (pinfunction "1_1") (pintype "passive"))
      (node (ref "SJ18") (pin "P$1") (pinfunction "1_P$1") (pintype "passive"))
      (node (ref "U$1") (pin "3V3") (pinfunction "3V3_3V3") (pintype "power_in"))
      (node (ref "U1") (pin "1") (pinfunction "SER_1") (pintype "input"))
      (node (ref "U1") (pin "16") (pinfunction "VCC_16") (pintype "power_in"))
      (node (ref "U1") (pin "9") (pinfunction "CLR_9") (pintype "input"))
      (node (ref "U2") (pin "16") (pinfunction "VCC_16") (pintype "power_in"))
      (node (ref "U2") (pin "9") (pinfunction "CLR_9") (pintype "input"))
    )
    (net (code "2") (name "+5V") (class "Default")
      (node (ref "C3") (pin "1") (pinfunction "1_1") (pintype "passive"))
      (node (ref "C5") (pin "1") (pinfunction "1_1") (pintype "passive"))
      (node (ref "C8") (pin "1") (pinfunction "1_1") (pintype "passive"))
      (node (ref "C9") (pin "1") (pinfunction "1_1") (pintype "passive"))
      (node (ref "JP1") (pin "3") (pinfunction "3_3") (pintype "passive"))
      (node (ref "JP2") (pin "6") (pinfunction "6_6") (pintype "passive"))
      (node (ref "JP5") (pin "3") (pinfunction "3_3") (pintype "passive"))
      (node (ref "JP5") (pin "4") (pinfunction "4_4") (pintype "passive"))
      (node (ref "JP6") (pin "3") (pinfunction "3_3") (pintype "passive"))
      (node (ref "JP6") (pin "4") (pinfunction "4_4") (pintype "passive"))
      (node (ref "JP7") (pin "3") (pinfunction "3_3") (pintype "passive"))
      (node (ref "JP7") (pin "4") (pinfunction "4_4") (pintype "passive"))
      (node (ref "JP8") (pin "3") (pinfunction "3_3") (pintype "passive"))
      (node (ref "JP8") (pin "4") (pinfunction "4_4") (pintype "passive"))
      (node (ref "PORTA") (pin "6") (pinfunction "6_6") (pintype "passive"))
      (node (ref "PORTB") (pin "6") (pinfunction "6_6") (pintype "passive"))
      (node (ref "PORTC") (pin "6") (pinfunction "6_6") (pintype "passive"))
      (node (ref "R19") (pin "2") (pinfunction "2_2") (pintype "passive"))
      (node (ref "R20") (pin "2") (pinfunction "2_2") (pintype "passive"))
      (node (ref "R21") (pin "2") (pinfunction "2_2") (pintype "passive"))
      (node (ref "R22") (pin "1") (pinfunction "1_1") (pintype "passive"))
      (node (ref "R23") (pin "1") (pinfunction "1_1") (pintype "passive"))
      (node (ref "R24") (pin "1") (pinfunction "1_1") (pintype "passive"))
      (node (ref "R25") (pin "1") (pinfunction "1_1") (pintype "passive"))
      (node (ref "R26") (pin "1") (pinfunction "1_1") (pintype "passive"))
      (node (ref "R27") (pin "1") (pinfunction "1_1") (pintype "passive"))
      (node (ref "R62") (pin "1") (pinfunction "1_1") (pintype "passive"))
      (node (ref "R63") (pin "1") (pinfunction "1_1") (pintype "passive"))
      (node (ref "R64") (pin "1") (pinfunction "1_1") (pintype "passive"))
      (node (ref "R65") (pin "1") (pinfunction "1_1") (pintype "passive"))
      (node (ref "R66") (pin "1") (pinfunction "1_1") (pintype "passive"))
      (node (ref "R67") (pin "1") (pinfunction "1_1") (pintype "passive"))
      (node (ref "SJ1") (pin "P$2") (pinfunction "2_P$2") (pintype "passive"))
      (node (ref "SJ10") (pin "P$2") (pinfunction "2_P$2") (pintype "passive"))
      (node (ref "SJ4") (pin "P$2") (pinfunction "2_P$2") (pintype "passive"))
      (node (ref "SJ7") (pin "P$2") (pinfunction "2_P$2") (pintype "passive"))
      (node (ref "U$1") (pin "5V2") (pinfunction "5V2_5V2") (pintype "power_in"))
      (node (ref "U11") (pin "10") (pinfunction "SCL_10") (pintype "input"))
      (node (ref "U11") (pin "16") (pinfunction "VCC_16") (pintype "power_in"))
      (node (ref "U13") (pin "10") (pinfunction "SCL_10") (pintype "input"))
      (node (ref "U13") (pin "16") (pinfunction "VCC_16") (pintype "power_in"))
      (node (ref "U7") (pin "3") (pinfunction "VCC_3") (pintype "power_in"))
      (node (ref "U7B") (pin "3") (pinfunction "VDD_3") (pintype "power_in"))
      (node (ref "X6") (pin "1") (pinfunction "1_1") (pintype "passive"))
    )
    (net (code "3") (name "+12V") (class "Default")
      (node (ref "C10") (pin "1") (pinfunction "1_1") (pintype "passive"))
      (node (ref "C6") (pin "1") (pinfunction "1_1") (pintype "passive"))
      (node (ref "C7") (pin "1") (pinfunction "1_1") (pintype "passive"))
      (node (ref "J3") (pin "1") (pinfunction "1_1") (pintype "passive"))
      (node (ref "JP2") (pin "7") (pinfunction "7_7") (pintype "passive"))
      (node (ref "JP4") (pin "2") (pinfunction "2_2") (pintype "passive"))
      (node (ref "SJ11") (pin "P$2") (pinfunction "2_P$2") (pintype "passive"))
      (node (ref "SJ14") (pin "P$2") (pinfunction "2_P$2") (pintype "passive"))
      (node (ref "SJ2") (pin "P$2") (pinfunction "2_P$2") (pintype "passive"))
      (node (ref "SJ5") (pin "P$2") (pinfunction "2_P$2") (pintype "passive"))
      (node (ref "SJ8") (pin "P$2") (pinfunction "2_P$2") (pintype "passive"))
      (node (ref "U10") (pin "4") (pinfunction "V+_4") (pintype "power_in"))
      (node (ref "U3") (pin "6") (pinfunction "VDD_6") (pintype "power_in"))
      (node (ref "U4") (pin "6") (pinfunction "VDD_6") (pintype "power_in"))
      (node (ref "U5") (pin "6") (pinfunction "VDD_6") (pintype "power_in"))
      (node (ref "U6") (pin "6") (pinfunction "VDD_6") (pintype "power_in"))
      (node (ref "U8") (pin "1") (pinfunction "VIN_1") (pintype "bidirectional"))
      (node (ref "U8B") (pin "5") (pinfunction "IN_5") (pintype "input"))
      (node (ref "U9") (pin "4") (pinfunction "V+_4") (pintype "power_in"))
    )
    (net (code "4") (name "/AGND") (class "Default")
      (node (ref "U$1") (pin "AGND") (pinfunction "AGND_AGND") (pintype "power_in"))
    )
    (net (code "5") (name "/AVDD") (class "Default")
      (node (ref "U$1") (pin "AVDD") (pinfunction "AVDD_AVDD") (pintype "power_in"))
    )
    (net (code "6") (name "/CANH") (class "Default")
      (node (ref "J1") (pin "1") (pinfunction "1_1") (pintype "passive"))
      (node (ref "J2") (pin "1") (pinfunction "1_1") (pintype "passive"))
      (node (ref "U7") (pin "7") (pinfunction "CANH_7") (pintype "bidirectional"))
      (node (ref "U7B") (pin "7") (pinfunction "CANH_7") (pintype "bidirectional"))
    )
    (net (code "7") (name "/CANL") (class "Default")
      (node (ref "J1") (pin "2") (pinfunction "2_2") (pintype "passive"))
      (node (ref "J2") (pin "2") (pinfunction "2_2") (pintype "passive"))
      (node (ref "U7") (pin "6") (pinfunction "CANL_6") (pintype "bidirectional"))
      (node (ref "U7B") (pin "6") (pinfunction "CANL_6") (pintype "bidirectional"))
    )
    (net (code "8") (name "/GND4") (class "Default")
      (node (ref "U$1") (pin "GND4") (pinfunction "GND4_GND4") (pintype "power_in"))
    )
    (net (code "9") (name "/PWR_POS") (class "Default")
      (node (ref "J1") (pin "8") (pinfunction "8_8") (pintype "passive"))
      (node (ref "J2") (pin "8") (pinfunction "8_8") (pintype "passive"))
      (node (ref "R40") (pin "2") (pinfunction "2_2") (pintype "passive"))
    )
    (net (code "10") (name "/U5V") (class "Default")
      (node (ref "U$1") (pin "U5V") (pinfunction "U5V_U5V") (pintype "power_in"))
    )
    (net (code "11") (name "/VBAT") (class "Default")
      (node (ref "U$1") (pin "VBAT") (pinfunction "VBAT_VBAT") (pintype "power_in"))
    )
    (net (code "12") (name "/VDD") (class "Default")
      (node (ref "U$1") (pin "VDD") (pinfunction "VDD_VDD") (pintype "power_in"))
    )
    (net (code "13") (name "CANRX") (class "Default")
      (node (ref "U$1") (pin "PB8") (pinfunction "PB8_PB8") (pintype "bidirectional"))
      (node (ref "U7") (pin "4") (pinfunction "RXD_4") (pintype "output"))
      (node (ref "U7B") (pin "4") (pinfunction "RXD_4") (pintype "bidirectional"))
    )
    (net (code "14") (name "CANTX") (class "Default")
      (node (ref "U$1") (pin "PB9") (pinfunction "PB9_PB9") (pintype "bidirectional"))
      (node (ref "U7") (pin "1") (pinfunction "TXD_1") (pintype "input"))
      (node (ref "U7B") (pin "1") (pinfunction "TXD_1") (pintype "bidirectional"))
    )
    (net (code "15") (name "E_CS") (class "Default")
      (node (ref "JP2") (pin "4") (pinfunction "4_4") (pintype "passive"))
      (node (ref "R23") (pin "2") (pinfunction "2_2") (pintype "passive"))
      (node (ref "U$1") (pin "PC10") (pinfunction "PC10_PC10") (pintype "bidirectional"))
    )
    (net (code "16") (name "E_LAT") (class "Default")
      (node (ref "JP2") (pin "5") (pinfunction "5_5") (pintype "passive"))
      (node (ref "R22") (pin "2") (pinfunction "2_2") (pintype "passive"))
      (node (ref "U$1") (pin "PC11") (pinfunction "PC11_PC11") (pintype "bidirectional"))
    )
    (net (code "17") (name "GND") (class "Default")
      (node (ref "C1") (pin "2") (pinfunction "2_2") (pintype "passive"))
      (node (ref "C10") (pin "2") (pinfunction "2_2") (pintype "passive"))
      (node (ref "C11") (pin "2") (pinfunction "2_2") (pintype "passive"))
      (node (ref "C2") (pin "-") (pinfunction "-_-") (pintype "passive"))
      (node (ref "C3") (pin "2") (pinfunction "2_2") (pintype "passive"))
      (node (ref "C4") (pin "2") (pinfunction "2_2") (pintype "passive"))
      (node (ref "C5") (pin "2") (pinfunction "2_2") (pintype "passive"))
      (node (ref "C6") (pin "2") (pinfunction "2_2") (pintype "passive"))
      (node (ref "C7") (pin "2") (pinfunction "2_2") (pintype "passive"))
      (node (ref "C8") (pin "2") (pinfunction "2_2") (pintype "passive"))
      (node (ref "C9") (pin "2") (pinfunction "2_2") (pintype "passive"))
      (node (ref "D1") (pin "A") (pinfunction "A_A") (pintype "passive"))
      (node (ref "D3") (pin "A") (pinfunction "A_A") (pintype "passive"))
      (node (ref "J1") (pin "3") (pinfunction "3_3") (pintype "passive"))
      (node (ref "J1") (pin "6") (pinfunction "6_6") (pintype "passive"))
      (node (ref "J1") (pin "7") (pinfunction "7_7") (pintype "passive"))
      (node (ref "J2") (pin "3") (pinfunction "3_3") (pintype "passive"))
      (node (ref "J2") (pin "6") (pinfunction "6_6") (pintype "passive"))
      (node (ref "J2") (pin "7") (pinfunction "7_7") (pintype "passive"))
      (node (ref "J3") (pin "2") (pinfunction "2_2") (pintype "passive"))
      (node (ref "J3") (pin "3") (pinfunction "3_3") (pintype "passive"))
      (node (ref "JP1") (pin "4") (pinfunction "4_4") (pintype "passive"))
      (node (ref "JP2") (pin "8") (pinfunction "8_8") (pintype "passive"))
      (node (ref "JP5") (pin "5") (pinfunction "5_5") (pintype "passive"))
      (node (ref "JP5") (pin "6") (pinfunction "6_6") (pintype "passive"))
      (node (ref "JP6") (pin "5") (pinfunction "5_5") (pintype "passive"))
      (node (ref "JP6") (pin "6") (pinfunction "6_6") (pintype "passive"))
      (node (ref "JP7") (pin "5") (pinfunction "5_5") (pintype "passive"))
      (node (ref "JP7") (pin "6") (pinfunction "6_6") (pintype "passive"))
      (node (ref "JP8") (pin "5") (pinfunction "5_5") (pintype "passive"))
      (node (ref "JP8") (pin "6") (pinfunction "6_6") (pintype "passive"))
      (node (ref "PORTA") (pin "5") (pinfunction "5_5") (pintype "passive"))
      (node (ref "PORTB") (pin "5") (pinfunction "5_5") (pintype "passive"))
      (node (ref "PORTC") (pin "5") (pinfunction "5_5") (pintype "passive"))
      (node (ref "Q1") (pin "2") (pinfunction "S_2") (pintype "passive"))
      (node (ref "Q10") (pin "2") (pinfunction "S_2") (pintype "passive"))
      (node (ref "Q11") (pin "2") (pinfunction "S_2") (pintype "passive"))
      (node (ref "Q12") (pin "2") (pinfunction "S_2") (pintype "passive"))
      (node (ref "Q13") (pin "2") (pinfunction "S_2") (pintype "passive"))
      (node (ref "Q14") (pin "2") (pinfunction "S_2") (pintype "passive"))
      (node (ref "Q15") (pin "2") (pinfunction "S_2") (pintype "passive"))
      (node (ref "Q16") (pin "2") (pinfunction "S_2") (pintype "passive"))
      (node (ref "Q2") (pin "2") (pinfunction "S_2") (pintype "passive"))
      (node (ref "Q3") (pin "2") (pinfunction "S_2") (pintype "passive"))
      (node (ref "Q4") (pin "2") (pinfunction "S_2") (pintype "passive"))
      (node (ref "Q5") (pin "2") (pinfunction "S_2") (pintype "passive"))
      (node (ref "Q6") (pin "2") (pinfunction "S_2") (pintype "passive"))
      (node (ref "Q7") (pin "2") (pinfunction "S_2") (pintype "passive"))
      (node (ref "Q8") (pin "2") (pinfunction "S_2") (pintype "passive"))
      (node (ref "Q9") (pin "2") (pinfunction "S_2") (pintype "passive"))
      (node (ref "R2") (pin "1") (pinfunction "1_1") (pintype "passive"))
      (node (ref "R61") (pin "2") (pinfunction "2_2") (pintype "passive"))
      (node (ref "SJ12") (pin "P$2") (pinfunction "2_P$2") (pintype "passive"))
      (node (ref "SJ3") (pin "2") (pinfunction "2_2") (pintype "passive"))
      (node (ref "SJ6") (pin "P$2") (pinfunction "2_P$2") (pintype "passive"))
      (node (ref "SJ9") (pin "2") (pinfunction "2_2") (pintype "passive"))
      (node (ref "U$1") (pin "GND3") (pinfunction "GND3_GND3") (pintype "power_in"))
      (node (ref "U$1") (pin "GND5") (pinfunction "GND5_GND5") (pintype "power_in"))
      (node (ref "U$1") (pin "GND6") (pinfunction "GND6_GND6") (pintype "power_in"))
      (node (ref "U$1") (pin "GND7") (pinfunction "GND7_GND7") (pintype "power_in"))
      (node (ref "U$1") (pin "GND8") (pinfunction "GND8_GND8") (pintype "power_in"))
      (node (ref "U1") (pin "6") (pinfunction "INH_6") (pintype "input"))
      (node (ref "U1") (pin "8") (pinfunction "GND_8") (pintype "power_in"))
      (node (ref "U10") (pin "11") (pinfunction "V-_11") (pintype "power_in"))
      (node (ref "U11") (pin "13") (pinfunction "G_13") (pintype "input"))
      (node (ref "U11") (pin "8") (pinfunction "GND_8") (pintype "power_in"))
      (node (ref "U13") (pin "13") (pinfunction "G_13") (pintype "input"))
      (node (ref "U13") (pin "8") (pinfunction "GND_8") (pintype "power_in"))
      (node (ref "U2") (pin "6") (pinfunction "INH_6") (pintype "input"))
      (node (ref "U2") (pin "8") (pinfunction "GND_8") (pintype "power_in"))
      (node (ref "U3") (pin "3") (pinfunction "VSS_3") (pintype "power_in"))
      (node (ref "U4") (pin "3") (pinfunction "VSS_3") (pintype "power_in"))
      (node (ref "U5") (pin "3") (pinfunction "VSS_3") (pintype "power_in"))
      (node (ref "U6") (pin "3") (pinfunction "VSS_3") (pintype "power_in"))
      (node (ref "U7") (pin "2") (pinfunction "GND_2") (pintype "power_in"))
      (node (ref "U7B") (pin "2") (pinfunction "VSS_2") (pintype "power_in"))
      (node (ref "U8") (pin "4") (pinfunction "SD_4") (pintype "bidirectional"))
      (node (ref "U8") (pin "5") (pinfunction "GND1_5") (pintype "power_in"))
      (node (ref "U8") (pin "6") (pinfunction "GND2_6") (pintype "power_in"))
      (node (ref "U8") (pin "7") (pinfunction "GND3_7") (pintype "power_in"))
      (node (ref "U8") (pin "8") (pinfunction "GND4_8") (pintype "power_in"))
      (node (ref "U8B") (pin "2") (pinfunction "GNDSIG_2") (pintype "input"))
      (node (ref "U8B") (pin "3") (pinfunction "~{ON/OFF}_3") (pintype "input"))
      (node (ref "U8B") (pin "4") (pinfunction "GND_4") (pintype "power_in"))
      (node (ref "U9") (pin "11") (pinfunction "V-_11") (pintype "power_in"))
      (node (ref "X6") (pin "2") (pinfunction "2_2") (pintype "passive"))
    )
    (net (code "18") (name "I2CSCL") (class "Default")
      (node (ref "JP1") (pin "1") (pinfunction "1_1") (pintype "passive"))
      (node (ref "R62") (pin "2") (pinfunction "2_2") (pintype "passive"))
      (node (ref "U$1") (pin "PB6") (pinfunction "PB6_PB6") (pintype "bidirectional"))
    )
    (net (code "19") (name "I2CSDA") (class "Default")
      (node (ref "JP1") (pin "2") (pinfunction "2_2") (pintype "passive"))
      (node (ref "R63") (pin "2") (pinfunction "2_2") (pintype "passive"))
      (node (ref "U$1") (pin "PB7") (pinfunction "PB7_PB7") (pintype "bidirectional"))
    )
    (net (code "20") (name "ILAT") (class "Default")
      (node (ref "U$1") (pin "PA6") (pinfunction "PA6_PA6") (pintype "bidirectional"))
      (node (ref "U1") (pin "15") (pinfunction "SH/~{LD}_15") (pintype "input"))
      (node (ref "U2") (pin "15") (pinfunction "SH/~{LD}_15") (pintype "input"))
    )
    (net (code "21") (name "MISO") (class "Default")
      (node (ref "JP2") (pin "1") (pinfunction "1_1") (pintype "passive"))
      (node (ref "U$1") (pin "PB4") (pinfunction "PB4_PB4") (pintype "bidirectional"))
    )
    (net (code "22") (name "MISO2") (class "Default")
      (node (ref "SJ13") (pin "P$2") (pinfunction "2_P$2") (pintype "passive"))
      (node (ref "SJ19") (pin "P$2") (pinfunction "2_P$2") (pintype "passive"))
      (node (ref "U$1") (pin "PC2") (pinfunction "PC2_PC2") (pintype "bidirectional"))
      (node (ref "U2") (pin "13") (pinfunction "QH_13") (pintype "output"))
    )
    (net (code "23") (name "MOSI") (class "Default")
      (node (ref "R20") (pin "1") (pinfunction "1_1") (pintype "passive"))
      (node (ref "SJ15") (pin "1") (pinfunction "1_1") (pintype "passive"))
      (node (ref "SJ17") (pin "P$2") (pinfunction "2_P$2") (pintype "passive"))
      (node (ref "U$1") (pin "PB5") (pinfunction "PB5_PB5") (pintype "bidirectional"))
      (node (ref "U11") (pin "14") (pinfunction "SER_14") (pintype "input"))
    )
    (net (code "24") (name "Net-(D2-PadA)") (class "Default")
      (node (ref "D2") (pin "A") (pinfunction "A_A") (pintype "passive"))
      (node (ref "D4") (pin "A") (pinfunction "A_A") (pintype "passive"))
      (node (ref "JP4") (pin "4") (pinfunction "4_4") (pintype "passive"))
    )
    (net (code "25") (name "Net-(D2-PadC)") (class "Default")
      (node (ref "D2") (pin "C") (pinfunction "C_C") (pintype "passive"))
      (node (ref "D4") (pin "C") (pinfunction "C_C") (pintype "passive"))
      (node (ref "JP4") (pin "1") (pinfunction "1_1") (pintype "passive"))
    )
    (net (code "26") (name "Net-(J1-Pad4)") (class "Default")
      (node (ref "J1") (pin "4") (pinfunction "4_4") (pintype "passive"))
      (node (ref "J2") (pin "4") (pinfunction "4_4") (pintype "passive"))
    )
    (net (code "27") (name "Net-(J1-Pad5)") (class "Default")
      (node (ref "J1") (pin "5") (pinfunction "5_5") (pintype "passive"))
      (node (ref "J2") (pin "5") (pinfunction "5_5") (pintype "passive"))
    )
    (net (code "28") (name "Net-(JP4-Pad3)") (class "Default")
      (node (ref "JP4") (pin "3") (pinfunction "3_3") (pintype "passive"))
      (node (ref "R40") (pin "1") (pinfunction "1_1") (pintype "passive"))
    )
    (net (code "29") (name "Net-(PORTA-Pad1)") (class "Default")
      (node (ref "PORTA") (pin "1") (pinfunction "1_1") (pintype "passive"))
      (node (ref "R44") (pin "2") (pinfunction "2_2") (pintype "passive"))
      (node (ref "R53") (pin "2") (pinfunction "2_2") (pintype "passive"))
      (node (ref "RN3") (pin "1") (pinfunction "1_1") (pintype "passive"))
      (node (ref "RN4") (pin "9") (pinfunction "9_9") (pintype "passive"))
      (node (ref "X1") (pin "1") (pinfunction "1_1") (pintype "passive"))
    )
    (net (code "30") (name "Net-(PORTB-Pad1)") (class "Default")
      (node (ref "PORTB") (pin "1") (pinfunction "1_1") (pintype "passive"))
      (node (ref "R35") (pin "2") (pinfunction "2_2") (pintype "passive"))
      (node (ref "R45") (pin "2") (pinfunction "2_2") (pintype "passive"))
      (node (ref "RN1") (pin "1") (pinfunction "1_1") (pintype "passive"))
      (node (ref "RN2") (pin "9") (pinfunction "9_9") (pintype "passive"))
      (node (ref "X2") (pin "1") (pinfunction "1_1") (pintype "passive"))
    )
    (net (code "31") (name "Net-(Q1-D)") (class "Default")
      (node (ref "Q1") (pin "3") (pinfunction "D_3") (pintype "passive"))
      (node (ref "U12") (pin "18") (pinfunction "O1_18") (pintype "open_collector"))
      (node (ref "X5") (pin "1") (pinfunction "1_1") (pintype "passive"))
    )
    (net (code "32") (name "Net-(Q1-G)") (class "Default")
      (node (ref "Q1") (pin "1") (pinfunction "G_1") (pintype "passive"))
      (node (ref "R3") (pin "2") (pinfunction "2_2") (pintype "passive"))
    )
    (net (code "33") (name "Net-(Q2-D)") (class "Default")
      (node (ref "Q2") (pin "3") (pinfunction "D_3") (pintype "passive"))
      (node (ref "U12") (pin "17") (pinfunction "O2_17") (pintype "open_collector"))
      (node (ref "X5") (pin "2") (pinfunction "2_2") (pintype "passive"))
    )
    (net (code "34") (name "Net-(Q2-G)") (class "Default")
      (node (ref "Q2") (pin "1") (pinfunction "G_1") (pintype "passive"))
      (node (ref "R4") (pin "2") (pinfunction "2_2") (pintype "passive"))
    )
    (net (code "35") (name "Net-(Q3-D)") (class "Default")
      (node (ref "Q3") (pin "3") (pinfunction "D_3") (pintype "passive"))
      (node (ref "U12") (pin "16") (pinfunction "O3_16") (pintype "open_collector"))
      (node (ref "X5") (pin "3") (pinfunction "3_3") (pintype "passive"))
    )
    (net (code "36") (name "Net-(Q3-G)") (class "Default")
      (node (ref "Q3") (pin "1") (pinfunction "G_1") (pintype "passive"))
      (node (ref "R5") (pin "2") (pinfunction "2_2") (pintype "passive"))
    )
    (net (code "37") (name "Net-(Q4-D)") (class "Default")
      (node (ref "Q4") (pin "3") (pinfunction "D_3") (pintype "passive"))
      (node (ref "U12") (pin "15") (pinfunction "O4_15") (pintype "open_collector"))
      (node (ref "X5") (pin "4") (pinfunction "4_4") (pintype "passive"))
    )
    (net (code "38") (name "Net-(Q4-G)") (class "Default")
      (node (ref "Q4") (pin "1") (pinfunction "G_1") (pintype "passive"))
      (node (ref "R6") (pin "2") (pinfunction "2_2") (pintype "passive"))
    )
    (net (code "39") (name "Net-(Q5-D)") (class "Default")
      (node (ref "Q5") (pin "3") (pinfunction "D_3") (pintype "passive"))
      (node (ref "U12") (pin "14") (pinfunction "O5_14") (pintype "open_collector"))
      (node (ref "X5") (pin "5") (pinfunction "5_5") (pintype "passive"))
    )
    (net (code "40") (name "Net-(Q5-G)") (class "Default")
      (node (ref "Q5") (pin "1") (pinfunction "G_1") (pintype "passive"))
      (node (ref "R7") (pin "2") (pinfunction "2_2") (pintype "passive"))
    )
    (net (code "41") (name "Net-(Q6-D)") (class "Default")
      (node (ref "Q6") (pin "3") (pinfunction "D_3") (pintype "passive"))
      (node (ref "U12") (pin "13") (pinfunction "O6_13") (pintype "open_collector"))
      (node (ref "X5") (pin "6") (pinfunction "6_6") (pintype "passive"))
    )
    (net (code "42") (name "Net-(Q6-G)") (class "Default")
      (node (ref "Q6") (pin "1") (pinfunction "G_1") (pintype "passive"))
      (node (ref "R8") (pin "2") (pinfunction "2_2") (pintype "passive"))
    )
    (net (code "43") (name "Net-(Q7-D)") (class "Default")
      (node (ref "Q7") (pin "3") (pinfunction "D_3") (pintype "passive"))
      (node (ref "U12") (pin "12") (pinfunction "O7_12") (pintype "open_collector"))
      (node (ref "X5") (pin "7") (pinfunction "7_7") (pintype "passive"))
    )
    (net (code "44") (name "Net-(Q7-G)") (class "Default")
      (node (ref "Q7") (pin "1") (pinfunction "G_1") (pintype "passive"))
      (node (ref "R9") (pin "2") (pinfunction "2_2") (pintype "passive"))
    )
    (net (code "45") (name "Net-(Q8-D)") (class "Default")
      (node (ref "Q8") (pin "3") (pinfunction "D_3") (pintype "passive"))
      (node (ref "U12") (pin "11") (pinfunction "O8_11") (pintype "open_collector"))
      (node (ref "X5") (pin "8") (pinfunction "8_8") (pintype "passive"))
    )
    (net (code "46") (name "Net-(Q8-G)") (class "Default")
      (node (ref "Q8") (pin "1") (pinfunction "G_1") (pintype "passive"))
      (node (ref "R10") (pin "2") (pinfunction "2_2") (pintype "passive"))
    )
    (net (code "47") (name "Net-(Q9-D)") (class "Default")
      (node (ref "Q9") (pin "3") (pinfunction "D_3") (pintype "passive"))
      (node (ref "U14") (pin "18") (pinfunction "O1_18") (pintype "open_collector"))
      (node (ref "X4") (pin "1") (pinfunction "1_1") (pintype "passive"))
    )
    (net (code "48") (name "Net-(Q9-G)") (class "Default")
      (node (ref "Q9") (pin "1") (pinfunction "G_1") (pintype "passive"))
      (node (ref "R11") (pin "2") (pinfunction "2_2") (pintype "passive"))
    )
    (net (code "49") (name "Net-(Q10-D)") (class "Default")
      (node (ref "Q10") (pin "3") (pinfunction "D_3") (pintype "passive"))
      (node (ref "U14") (pin "17") (pinfunction "O2_17") (pintype "open_collector"))
      (node (ref "X4") (pin "2") (pinfunction "2_2") (pintype "passive"))
    )
    (net (code "50") (name "Net-(Q10-G)") (class "Default")
      (node (ref "Q10") (pin "1") (pinfunction "G_1") (pintype "passive"))
      (node (ref "R12") (pin "2") (pinfunction "2_2") (pintype "passive"))
    )
    (net (code "51") (name "Net-(Q11-D)") (class "Default")
      (node (ref "Q11") (pin "3") (pinfunction "D_3") (pintype "passive"))
      (node (ref "U14") (pin "16") (pinfunction "O3_16") (pintype "open_collector"))
      (node (ref "X4") (pin "3") (pinfunction "3_3") (pintype "passive"))
    )
    (net (code "52") (name "Net-(Q11-G)") (class "Default")
      (node (ref "Q11") (pin "1") (pinfunction "G_1") (pintype "passive"))
      (node (ref "R13") (pin "2") (pinfunction "2_2") (pintype "passive"))
    )
    (net (code "53") (name "Net-(Q12-D)") (class "Default")
      (node (ref "Q12") (pin "3") (pinfunction "D_3") (pintype "passive"))
      (node (ref "U14") (pin "15") (pinfunction "O4_15") (pintype "open_collector"))
      (node (ref "X4") (pin "4") (pinfunction "4_4") (pintype "passive"))
    )
    (net (code "54") (name "Net-(Q12-G)") (class "Default")
      (node (ref "Q12") (pin "1") (pinfunction "G_1") (pintype "passive"))
      (node (ref "R14") (pin "2") (pinfunction "2_2") (pintype "passive"))
    )
    (net (code "55") (name "Net-(Q13-D)") (class "Default")
      (node (ref "Q13") (pin "3") (pinfunction "D_3") (pintype "passive"))
      (node (ref "U14") (pin "14") (pinfunction "O5_14") (pintype "open_collector"))
      (node (ref "X4") (pin "5") (pinfunction "5_5") (pintype "passive"))
    )
    (net (code "56") (name "Net-(Q13-G)") (class "Default")
      (node (ref "Q13") (pin "1") (pinfunction "G_1") (pintype "passive"))
      (node (ref "R15") (pin "2") (pinfunction "2_2") (pintype "passive"))
    )
    (net (code "57") (name "Net-(Q14-D)") (class "Default")
      (node (ref "Q14") (pin "3") (pinfunction "D_3") (pintype "passive"))
      (node (ref "U14") (pin "13") (pinfunction "O6_13") (pintype "open_collector"))
      (node (ref "X4") (pin "6") (pinfunction "6_6") (pintype "passive"))
    )
    (net (code "58") (name "Net-(Q14-G)") (class "Default")
      (node (ref "Q14") (pin "1") (pinfunction "G_1") (pintype "passive"))
      (node (ref "R16") (pin "2") (pinfunction "2_2") (pintype "passive"))
    )
    (net (code "59") (name "Net-(Q15-D)") (class "Default")
      (node (ref "Q15") (pin "3") (pinfunction "D_3") (pintype "passive"))
      (node (ref "U14") (pin "12") (pinfunction "O7_12") (pintype "open_collector"))
      (node (ref "X4") (pin "7") (pinfunction "7_7") (pintype "passive"))
    )
    (net (code "60") (name "Net-(Q15-G)") (class "Default")
      (node (ref "Q15") (pin "1") (pinfunction "G_1") (pintype "passive"))
      (node (ref "R17") (pin "2") (pinfunction "2_2") (pintype "passive"))
    )
    (net (code "61") (name "Net-(Q16-D)") (class "Default")
      (node (ref "Q16") (pin "3") (pinfunction "D_3") (pintype "passive"))
      (node (ref "U14") (pin "11") (pinfunction "O8_11") (pintype "open_collector"))
      (node (ref "X4") (pin "8") (pinfunction "8_8") (pintype "passive"))
    )
    (net (code "62") (name "Net-(Q16-G)") (class "Default")
      (node (ref "Q16") (pin "1") (pinfunction "G_1") (pintype "passive"))
      (node (ref "R18") (pin "2") (pinfunction "2_2") (pintype "passive"))
    )
    (net (code "63") (name "Net-(RN1A-2)") (class "Default")
      (node (ref "R35") (pin "1") (pinfunction "1_1") (pintype "passive"))
      (node (ref "RN1") (pin "16") (pinfunction "2_16") (pintype "passive"))
      (node (ref "U2") (pin "14") (pinfunction "H_14") (pintype "input"))
    )
    (net (code "64") (name "Net-(RN1B-1)") (class "Default")
      (node (ref "PORTB") (pin "2") (pinfunction "2_2") (pintype "passive"))
      (node (ref "R34") (pin "2") (pinfunction "2_2") (pintype "passive"))
      (node (ref "R46") (pin "2") (pinfunction "2_2") (pintype "passive"))
      (node (ref "RN1") (pin "2") (pinfunction "1_2") (pintype "passive"))
      (node (ref "RN2") (pin "8") (pinfunction "8_8") (pintype "passive"))
      (node (ref "X2") (pin "2") (pinfunction "2_2") (pintype "passive"))
    )
    (net (code "65") (name "Net-(RN1B-2)") (class "Default")
      (node (ref "R34") (pin "1") (pinfunction "1_1") (pintype "passive"))
      (node (ref "RN1") (pin "15") (pinfunction "2_15") (pintype "passive"))
      (node (ref "U2") (pin "12") (pinfunction "G_12") (pintype "input"))
    )
    (net (code "66") (name "Net-(RN1C-1)") (class "Default")
      (node (ref "PORTB") (pin "3") (pinfunction "3_3") (pintype "passive"))
      (node (ref "R33") (pin "2") (pinfunction "2_2") (pintype "passive"))
      (node (ref "R47") (pin "2") (pinfunction "2_2") (pintype "passive"))
      (node (ref "RN1") (pin "3") (pinfunction "1_3") (pintype "passive"))
      (node (ref "RN2") (pin "7") (pinfunction "7_7") (pintype "passive"))
      (node (ref "X2") (pin "3") (pinfunction "3_3") (pintype "passive"))
    )
    (net (code "67") (name "Net-(RN1C-2)") (class "Default")
      (node (ref "R33") (pin "1") (pinfunction "1_1") (pintype "passive"))
      (node (ref "RN1") (pin "14") (pinfunction "2_14") (pintype "passive"))
      (node (ref "U2") (pin "11") (pinfunction "F_11") (pintype "input"))
    )
    (net (code "68") (name "Net-(RN1D-1)") (class "Default")
      (node (ref "PORTB") (pin "4") (pinfunction "4_4") (pintype "passive"))
      (node (ref "R32") (pin "2") (pinfunction "2_2") (pintype "passive"))
      (node (ref "R48") (pin "2") (pinfunction "2_2") (pintype "passive"))
      (node (ref "RN1") (pin "4") (pinfunction "1_4") (pintype "passive"))
      (node (ref "RN2") (pin "6") (pinfunction "6_6") (pintype "passive"))
      (node (ref "X2") (pin "4") (pinfunction "4_4") (pintype "passive"))
    )
    (net (code "69") (name "Net-(RN1D-2)") (class "Default")
      (node (ref "R32") (pin "1") (pinfunction "1_1") (pintype "passive"))
      (node (ref "RN1") (pin "13") (pinfunction "2_13") (pintype "passive"))
      (node (ref "U2") (pin "10") (pinfunction "E_10") (pintype "input"))
    )
    (net (code "70") (name "Net-(RN1E-1)") (class "Default")
      (node (ref "PORTB") (pin "7") (pinfunction "7_7") (pintype "passive"))
      (node (ref "R31") (pin "2") (pinfunction "2_2") (pintype "passive"))
      (node (ref "R49") (pin "2") (pinfunction "2_2") (pintype "passive"))
      (node (ref "RN1") (pin "5") (pinfunction "1_5") (pintype "passive"))
      (node (ref "RN2") (pin "5") (pinfunction "5_5") (pintype "passive"))
      (node (ref "X2") (pin "5") (pinfunction "5_5") (pintype "passive"))
    )
    (net (code "71") (name "Net-(RN1E-2)") (class "Default")
      (node (ref "R31") (pin "1") (pinfunction "1_1") (pintype "passive"))
      (node (ref "RN1") (pin "12") (pinfunction "2_12") (pintype "passive"))
      (node (ref "U2") (pin "5") (pinfunction "D_5") (pintype "input"))
    )
    (net (code "72") (name "Net-(RN1F-1)") (class "Default")
      (node (ref "PORTB") (pin "8") (pinfunction "8_8") (pintype "passive"))
      (node (ref "R30") (pin "2") (pinfunction "2_2") (pintype "passive"))
      (node (ref "R50") (pin "2") (pinfunction "2_2") (pintype "passive"))
      (node (ref "RN1") (pin "6") (pinfunction "1_6") (pintype "passive"))
      (node (ref "RN2") (pin "4") (pinfunction "4_4") (pintype "passive"))
      (node (ref "X2") (pin "6") (pinfunction "6_6") (pintype "passive"))
    )
    (net (code "73") (name "Net-(RN1F-2)") (class "Default")
      (node (ref "R30") (pin "1") (pinfunction "1_1") (pintype "passive"))
      (node (ref "RN1") (pin "11") (pinfunction "2_11") (pintype "passive"))
      (node (ref "U2") (pin "4") (pinfunction "C_4") (pintype "input"))
    )
    (net (code "74") (name "Net-(RN1G-1)") (class "Default")
      (node (ref "PORTB") (pin "9") (pinfunction "9_9") (pintype "passive"))
      (node (ref "R29") (pin "2") (pinfunction "2_2") (pintype "passive"))
      (node (ref "R51") (pin "2") (pinfunction "2_2") (pintype "passive"))
      (node (ref "RN1") (pin "7") (pinfunction "1_7") (pintype "passive"))
      (node (ref "RN2") (pin "3") (pinfunction "3_3") (pintype "passive"))
      (node (ref "X2") (pin "7") (pinfunction "7_7") (pintype "passive"))
    )
    (net (code "75") (name "Net-(RN1G-2)") (class "Default")
      (node (ref "R29") (pin "1") (pinfunction "1_1") (pintype "passive"))
      (node (ref "RN1") (pin "10") (pinfunction "2_10") (pintype "passive"))
      (node (ref "U2") (pin "3") (pinfunction "B_3") (pintype "input"))
    )
    (net (code "76") (name "Net-(RN1H-1)") (class "Default")
      (node (ref "PORTB") (pin "10") (pinfunction "10_10") (pintype "passive"))
      (node (ref "R28") (pin "2") (pinfunction "2_2") (pintype "passive"))
      (node (ref "R52") (pin "2") (pinfunction "2_2") (pintype "passive"))
      (node (ref "RN1") (pin "8") (pinfunction "1_8") (pintype "passive"))
      (node (ref "RN2") (pin "2") (pinfunction "2_2") (pintype "passive"))
      (node (ref "X2") (pin "8") (pinfunction "8_8") (pintype "passive"))
    )
    (net (code "77") (name "Net-(RN1H-2)") (class "Default")
      (node (ref "R28") (pin "1") (pinfunction "1_1") (pintype "passive"))
      (node (ref "RN1") (pin "9") (pinfunction "2_9") (pintype "passive"))
      (node (ref "U2") (pin "2") (pinfunction "A_2") (pintype "input"))
    )
    (net (code "78") (name "Net-(RN3A-2)") (class "Default")
      (node (ref "R44") (pin "1") (pinfunction "1_1") (pintype "passive"))
      (node (ref "RN3") (pin "16") (pinfunction "2_16") (pintype "passive"))
      (node (ref "U1") (pin "14") (pinfunction "H_14") (pintype "input"))
    )
    (net (code "79") (name "Net-(RN3B-1)") (class "Default")
      (node (ref "PORTA") (pin "2") (pinfunction "2_2") (pintype "passive"))
      (node (ref "R43") (pin "2") (pinfunction "2_2") (pintype "passive"))
      (node (ref "R54") (pin "2") (pinfunction "2_2") (pintype "passive"))
      (node (ref "RN3") (pin "2") (pinfunction "1_2") (pintype "passive"))
      (node (ref "RN4") (pin "8") (pinfunction "8_8") (pintype "passive"))
      (node (ref "X1") (pin "2") (pinfunction "2_2") (pintype "passive"))
    )
    (net (code "80") (name "Net-(RN3B-2)") (class "Default")
      (node (ref "R43") (pin "1") (pinfunction "1_1") (pintype "passive"))
      (node (ref "RN3") (pin "15") (pinfunction "2_15") (pintype "passive"))
      (node (ref "U1") (pin "12") (pinfunction "G_12") (pintype "input"))
    )
    (net (code "81") (name "Net-(RN3C-1)") (class "Default")
      (node (ref "PORTA") (pin "3") (pinfunction "3_3") (pintype "passive"))
      (node (ref "R42") (pin "2") (pinfunction "2_2") (pintype "passive"))
      (node (ref "R55") (pin "2") (pinfunction "2_2") (pintype "passive"))
      (node (ref "RN3") (pin "3") (pinfunction "1_3") (pintype "passive"))
      (node (ref "RN4") (pin "7") (pinfunction "7_7") (pintype "passive"))
      (node (ref "X1") (pin "3") (pinfunction "3_3") (pintype "passive"))
    )
    (net (code "82") (name "Net-(RN3C-2)") (class "Default")
      (node (ref "R42") (pin "1") (pinfunction "1_1") (pintype "passive"))
      (node (ref "RN3") (pin "14") (pinfunction "2_14") (pintype "passive"))
      (node (ref "U1") (pin "11") (pinfunction "F_11") (pintype "input"))
    )
    (net (code "83") (name "Net-(RN3D-1)") (class "Default")
      (node (ref "PORTA") (pin "4") (pinfunction "4_4") (pintype "passive"))
      (node (ref "R41") (pin "2") (pinfunction "2_2") (pintype "passive"))
      (node (ref "R56") (pin "2") (pinfunction "2_2") (pintype "passive"))
      (node (ref "RN3") (pin "4") (pinfunction "1_4") (pintype "passive"))
      (node (ref "RN4") (pin "6") (pinfunction "6_6") (pintype "passive"))
      (node (ref "X1") (pin "4") (pinfunction "4_4") (pintype "passive"))
    )
    (net (code "84") (name "Net-(RN3D-2)") (class "Default")
      (node (ref "R41") (pin "1") (pinfunction "1_1") (pintype "passive"))
      (node (ref "RN3") (pin "13") (pinfunction "2_13") (pintype "passive"))
      (node (ref "U1") (pin "10") (pinfunction "E_10") (pintype "input"))
    )
    (net (code "85") (name "Net-(RN3E-1)") (class "Default")
      (node (ref "PORTA") (pin "7") (pinfunction "7_7") (pintype "passive"))
      (node (ref "R39") (pin "2") (pinfunction "2_2") (pintype "passive"))
      (node (ref "R57") (pin "2") (pinfunction "2_2") (pintype "passive"))
      (node (ref "RN3") (pin "5") (pinfunction "1_5") (pintype "passive"))
      (node (ref "RN4") (pin "5") (pinfunction "5_5") (pintype "passive"))
      (node (ref "X1") (pin "5") (pinfunction "5_5") (pintype "passive"))
    )
    (net (code "86") (name "Net-(RN3E-2)") (class "Default")
      (node (ref "R39") (pin "1") (pinfunction "1_1") (pintype "passive"))
      (node (ref "RN3") (pin "12") (pinfunction "2_12") (pintype "passive"))
      (node (ref "U1") (pin "5") (pinfunction "D_5") (pintype "input"))
    )
    (net (code "87") (name "Net-(RN3F-1)") (class "Default")
      (node (ref "PORTA") (pin "8") (pinfunction "8_8") (pintype "passive"))
      (node (ref "R38") (pin "2") (pinfunction "2_2") (pintype "passive"))
      (node (ref "R58") (pin "2") (pinfunction "2_2") (pintype "passive"))
      (node (ref "RN3") (pin "6") (pinfunction "1_6") (pintype "passive"))
      (node (ref "RN4") (pin "4") (pinfunction "4_4") (pintype "passive"))
      (node (ref "X1") (pin "6") (pinfunction "6_6") (pintype "passive"))
    )
    (net (code "88") (name "Net-(RN3F-2)") (class "Default")
      (node (ref "R38") (pin "1") (pinfunction "1_1") (pintype "passive"))
      (node (ref "RN3") (pin "11") (pinfunction "2_11") (pintype "passive"))
      (node (ref "U1") (pin "4") (pinfunction "C_4") (pintype "input"))
    )
    (net (code "89") (name "Net-(RN3G-1)") (class "Default")
      (node (ref "PORTA") (pin "9") (pinfunction "9_9") (pintype "passive"))
      (node (ref "R37") (pin "2") (pinfunction "2_2") (pintype "passive"))
      (node (ref "R59") (pin "2") (pinfunction "2_2") (pintype "passive"))
      (node (ref "RN3") (pin "7") (pinfunction "1_7") (pintype "passive"))
      (node (ref "RN4") (pin "3") (pinfunction "3_3") (pintype "passive"))
      (node (ref "X1") (pin "7") (pinfunction "7_7") (pintype "passive"))
    )
    (net (code "90") (name "Net-(RN3G-2)") (class "Default")
      (node (ref "R37") (pin "1") (pinfunction "1_1") (pintype "passive"))
      (node (ref "RN3") (pin "10") (pinfunction "2_10") (pintype "passive"))
      (node (ref "U1") (pin "3") (pinfunction "B_3") (pintype "input"))
    )
    (net (code "91") (name "Net-(RN3H-1)") (class "Default")
      (node (ref "PORTA") (pin "10") (pinfunction "10_10") (pintype "passive"))
      (node (ref "R36") (pin "2") (pinfunction "2_2") (pintype "passive"))
      (node (ref "R60") (pin "2") (pinfunction "2_2") (pintype "passive"))
      (node (ref "RN3") (pin "8") (pinfunction "1_8") (pintype "passive"))
      (node (ref "RN4") (pin "2") (pinfunction "2_2") (pintype "passive"))
      (node (ref "X1") (pin "8") (pinfunction "8_8") (pintype "passive"))
    )
    (net (code "92") (name "Net-(RN3H-2)") (class "Default")
      (node (ref "R36") (pin "1") (pinfunction "1_1") (pintype "passive"))
      (node (ref "RN3") (pin "9") (pinfunction "2_9") (pintype "passive"))
      (node (ref "U1") (pin "2") (pinfunction "A_2") (pintype "input"))
    )
    (net (code "93") (name "Net-(SJ1-1)") (class "Default")
      (node (ref "SJ1") (pin "P$1") (pinfunction "1_P$1") (pintype "passive"))
      (node (ref "SJ2") (pin "P$1") (pinfunction "1_P$1") (pintype "passive"))
      (node (ref "SJ3") (pin "1") (pinfunction "1_1") (pintype "passive"))
      (node (ref "U12") (pin "9") (pinfunction "GND_9") (pintype "power_in"))
    )
    (net (code "94") (name "Net-(SJ4-1)") (class "Default")
      (node (ref "SJ4") (pin "P$1") (pinfunction "1_P$1") (pintype "passive"))
      (node (ref "SJ5") (pin "P$1") (pinfunction "1_P$1") (pintype "passive"))
      (node (ref "SJ6") (pin "P$1") (pinfunction "1_P$1") (pintype "passive"))
      (node (ref "U12") (pin "10") (pinfunction "CD+_10") (pintype "passive"))
    )
    (net (code "95") (name "Net-(SJ7-1)") (class "Default")
      (node (ref "SJ7") (pin "P$1") (pinfunction "1_P$1") (pintype "passive"))
      (node (ref "SJ8") (pin "P$1") (pinfunction "1_P$1") (pintype "passive"))
      (node (ref "SJ9") (pin "1") (pinfunction "1_1") (pintype "passive"))
      (node (ref "U14") (pin "9") (pinfunction "GND_9") (pintype "power_in"))
    )
    (net (code "96") (name "Net-(SJ10-1)") (class "Default")
      (node (ref "SJ10") (pin "P$1") (pinfunction "1_P$1") (pintype "passive"))
      (node (ref "SJ11") (pin "P$1") (pinfunction "1_P$1") (pintype "passive"))
      (node (ref "SJ12") (pin "P$1") (pinfunction "1_P$1") (pintype "passive"))
      (node (ref "U14") (pin "10") (pinfunction "CD+_10") (pintype "passive"))
    )
    (net (code "97") (name "Net-(SJ13-1)") (class "Default")
      (node (ref "SJ13") (pin "P$1") (pinfunction "1_P$1") (pintype "passive"))
      (node (ref "U$1") (pin "PB14") (pinfunction "PB14_PB14") (pintype "bidirectional"))
    )
    (net (code "98") (name "Net-(SJ14-1)") (class "Default")
      (node (ref "SJ14") (pin "P$1") (pinfunction "1_P$1") (pintype "passive"))
      (node (ref "U$1") (pin "VIN2") (pinfunction "VIN2_VIN2") (pintype "power_in"))
    )
    (net (code "99") (name "Net-(SJ16-2)") (class "Default")
      (node (ref "JP2") (pin "2") (pinfunction "2_2") (pintype "passive"))
      (node (ref "SJ15") (pin "2") (pinfunction "2_2") (pintype "passive"))
      (node (ref "SJ16") (pin "P$2") (pinfunction "2_P$2") (pintype "passive"))
    )
    (net (code "100") (name "Net-(SJ18-2)") (class "Default")
      (node (ref "SJ18") (pin "P$2") (pinfunction "2_P$2") (pintype "passive"))
      (node (ref "U7") (pin "5") (pinfunction "VREF_5") (pintype "output"))
      (node (ref "U7B") (pin "5") (pinfunction "VREF_5") (pintype "bidirectional"))
    )
    (net (code "101") (name "Net-(U3A-O)") (class "Default")
      (node (ref "PORTC") (pin "1") (pinfunction "1_1") (pintype "passive"))
      (node (ref "U3") (pin "7") (pinfunction "O_7") (pintype "output"))
      (node (ref "U9") (pin "7") (pinfunction "OUT_7") (pintype "output"))
      (node (ref "X3") (pin "1") (pinfunction "1_1") (pintype "passive"))
    )
    (net (code "102") (name "Net-(U3B-O)") (class "Default")
      (node (ref "PORTC") (pin "2") (pinfunction "2_2") (pintype "passive"))
      (node (ref "U3") (pin "5") (pinfunction "O_5") (pintype "output"))
      (node (ref "U9") (pin "8") (pinfunction "OUT_8") (pintype "output"))
      (node (ref "X3") (pin "2") (pinfunction "2_2") (pintype "passive"))
    )
    (net (code "103") (name "Net-(U4A-O)") (class "Default")
      (node (ref "PORTC") (pin "4") (pinfunction "4_4") (pintype "passive"))
      (node (ref "U4") (pin "7") (pinfunction "O_7") (pintype "output"))
      (node (ref "U9") (pin "14") (pinfunction "OUT_14") (pintype "output"))
      (node (ref "X3") (pin "4") (pinfunction "4_4") (pintype "passive"))
    )
    (net (code "104") (name "Net-(U4B-O)") (class "Default")
      (node (ref "PORTC") (pin "3") (pinfunction "3_3") (pintype "passive"))
      (node (ref "U4") (pin "5") (pinfunction "O_5") (pintype "output"))
      (node (ref "U9") (pin "1") (pinfunction "OUT_1") (pintype "output"))
      (node (ref "X3") (pin "3") (pinfunction "3_3") (pintype "passive"))
    )
    (net (code "105") (name "Net-(U7-RS)") (class "Default")
      (node (ref "R61") (pin "1") (pinfunction "1_1") (pintype "passive"))
      (node (ref "U7") (pin "8") (pinfunction "RS_8") (pintype "input"))
      (node (ref "U7B") (pin "8") (pinfunction "RS_8") (pintype "bidirectional"))
    )
    (net (code "106") (name "Net-(U8-VOUT)") (class "Default")
      (node (ref "D1") (pin "C") (pinfunction "C_C") (pintype "passive"))
      (node (ref "D3") (pin "C") (pinfunction "C_C") (pintype "passive"))
      (node (ref "L1") (pin "2") (pinfunction "2_2") (pintype "passive"))
      (node (ref "U8") (pin "2") (pinfunction "VOUT_2") (pintype "bidirectional"))
      (node (ref "U8B") (pin "7") (pinfunction "OUT_7") (pintype "passive"))
    )
    (net (code "107") (name "Net-(U10A--IN)") (class "Default")
      (node (ref "R1") (pin "1") (pinfunction "1_1") (pintype "passive"))
      (node (ref "R2") (pin "2") (pinfunction "2_2") (pintype "passive"))
      (node (ref "U10") (pin "13") (pinfunction "-IN_13") (pintype "input"))
      (node (ref "U10") (pin "2") (pinfunction "-IN_2") (pintype "input"))
      (node (ref "U10") (pin "6") (pinfunction "-IN_6") (pintype "input"))
      (node (ref "U10") (pin "9") (pinfunction "-IN_9") (pintype "input"))
      (node (ref "U9") (pin "13") (pinfunction "-IN_13") (pintype "input"))
      (node (ref "U9") (pin "2") (pinfunction "-IN_2") (pintype "input"))
      (node (ref "U9") (pin "6") (pinfunction "-IN_6") (pintype "input"))
      (node (ref "U9") (pin "9") (pinfunction "-IN_9") (pintype "input"))
    )
    (net (code "108") (name "Net-(U10A-OUT)") (class "Default")
      (node (ref "PORTC") (pin "9") (pinfunction "9_9") (pintype "passive"))
      (node (ref "U10") (pin "1") (pinfunction "OUT_1") (pintype "output"))
      (node (ref "U6") (pin "5") (pinfunction "O_5") (pintype "output"))
      (node (ref "X3") (pin "7") (pinfunction "7_7") (pintype "passive"))
    )
    (net (code "109") (name "Net-(U10B-OUT)") (class "Default")
      (node (ref "PORTC") (pin "7") (pinfunction "7_7") (pintype "passive"))
      (node (ref "U10") (pin "7") (pinfunction "OUT_7") (pintype "output"))
      (node (ref "U5") (pin "7") (pinfunction "O_7") (pintype "output"))
      (node (ref "X3") (pin "5") (pinfunction "5_5") (pintype "passive"))
    )
    (net (code "110") (name "Net-(U10C-OUT)") (class "Default")
      (node (ref "PORTC") (pin "8") (pinfunction "8_8") (pintype "passive"))
      (node (ref "U10") (pin "8") (pinfunction "OUT_8") (pintype "output"))
      (node (ref "U5") (pin "5") (pinfunction "O_5") (pintype "output"))
      (node (ref "X3") (pin "6") (pinfunction "6_6") (pintype "passive"))
    )
    (net (code "111") (name "Net-(U10D-OUT)") (class "Default")
      (node (ref "PORTC") (pin "10") (pinfunction "10_10") (pintype "passive"))
      (node (ref "U10") (pin "14") (pinfunction "OUT_14") (pintype "output"))
      (node (ref "U6") (pin "7") (pinfunction "O_7") (pintype "output"))
      (node (ref "X3") (pin "8") (pinfunction "8_8") (pintype "passive"))
    )
    (net (code "112") (name "Net-(U11A-QA)") (class "Default")
      (node (ref "R3") (pin "1") (pinfunction "1_1") (pintype "passive"))
      (node (ref "U11") (pin "15") (pinfunction "QA_15") (pintype "tri_state"))
      (node (ref "U12") (pin "1") (pinfunction "I1_1") (pintype "input"))
    )
    (net (code "113") (name "Net-(U11A-QB)") (class "Default")
      (node (ref "R4") (pin "1") (pinfunction "1_1") (pintype "passive"))
      (node (ref "U11") (pin "1") (pinfunction "QB_1") (pintype "tri_state"))
      (node (ref "U12") (pin "2") (pinfunction "I2_2") (pintype "input"))
    )
    (net (code "114") (name "Net-(U11A-QC)") (class "Default")
      (node (ref "R5") (pin "1") (pinfunction "1_1") (pintype "passive"))
      (node (ref "U11") (pin "2") (pinfunction "QC_2") (pintype "tri_state"))
      (node (ref "U12") (pin "3") (pinfunction "I3_3") (pintype "input"))
    )
    (net (code "115") (name "Net-(U11A-QD)") (class "Default")
      (node (ref "R6") (pin "1") (pinfunction "1_1") (pintype "passive"))
      (node (ref "U11") (pin "3") (pinfunction "QD_3") (pintype "tri_state"))
      (node (ref "U12") (pin "4") (pinfunction "I4_4") (pintype "input"))
    )
    (net (code "116") (name "Net-(U11A-QE)") (class "Default")
      (node (ref "R7") (pin "1") (pinfunction "1_1") (pintype "passive"))
      (node (ref "U11") (pin "4") (pinfunction "QE_4") (pintype "tri_state"))
      (node (ref "U12") (pin "5") (pinfunction "I5_5") (pintype "input"))
    )
    (net (code "117") (name "Net-(U11A-QF)") (class "Default")
      (node (ref "R8") (pin "1") (pinfunction "1_1") (pintype "passive"))
      (node (ref "U11") (pin "5") (pinfunction "QF_5") (pintype "tri_state"))
      (node (ref "U12") (pin "6") (pinfunction "I6_6") (pintype "input"))
    )
    (net (code "118") (name "Net-(U11A-QG)") (class "Default")
      (node (ref "R9") (pin "1") (pinfunction "1_1") (pintype "passive"))
      (node (ref "U11") (pin "6") (pinfunction "QG_6") (pintype "tri_state"))
      (node (ref "U12") (pin "7") (pinfunction "I7_7") (pintype "input"))
    )
    (net (code "119") (name "Net-(U11A-QH)") (class "Default")
      (node (ref "R10") (pin "1") (pinfunction "1_1") (pintype "passive"))
      (node (ref "U11") (pin "7") (pinfunction "QH_7") (pintype "tri_state"))
      (node (ref "U12") (pin "8") (pinfunction "I8_8") (pintype "input"))
    )
    (net (code "120") (name "Net-(U13A-QA)") (class "Default")
      (node (ref "R11") (pin "1") (pinfunction "1_1") (pintype "passive"))
      (node (ref "U13") (pin "15") (pinfunction "QA_15") (pintype "tri_state"))
      (node (ref "U14") (pin "1") (pinfunction "I1_1") (pintype "input"))
    )
    (net (code "121") (name "Net-(U13A-QB)") (class "Default")
      (node (ref "R12") (pin "1") (pinfunction "1_1") (pintype "passive"))
      (node (ref "U13") (pin "1") (pinfunction "QB_1") (pintype "tri_state"))
      (node (ref "U14") (pin "2") (pinfunction "I2_2") (pintype "input"))
    )
    (net (code "122") (name "Net-(U13A-QC)") (class "Default")
      (node (ref "R13") (pin "1") (pinfunction "1_1") (pintype "passive"))
      (node (ref "U13") (pin "2") (pinfunction "QC_2") (pintype "tri_state"))
      (node (ref "U14") (pin "3") (pinfunction "I3_3") (pintype "input"))
    )
    (net (code "123") (name "Net-(U13A-QD)") (class "Default")
      (node (ref "R14") (pin "1") (pinfunction "1_1") (pintype "passive"))
      (node (ref "U13") (pin "3") (pinfunction "QD_3") (pintype "tri_state"))
      (node (ref "U14") (pin "4") (pinfunction "I4_4") (pintype "input"))
    )
    (net (code "124") (name "Net-(U13A-QE)") (class "Default")
      (node (ref "R15") (pin "1") (pinfunction "1_1") (pintype "passive"))
      (node (ref "U13") (pin "4") (pinfunction "QE_4") (pintype "tri_state"))
      (node (ref "U14") (pin "5") (pinfunction "I5_5") (pintype "input"))
    )
    (net (code "125") (name "Net-(U13A-QF)") (class "Default")
      (node (ref "R16") (pin "1") (pinfunction "1_1") (pintype "passive"))
      (node (ref "U13") (pin "5") (pinfunction "QF_5") (pintype "tri_state"))
      (node (ref "U14") (pin "6") (pinfunction "I6_6") (pintype "input"))
    )
    (net (code "126") (name "Net-(U13A-QG)") (class "Default")
      (node (ref "R17") (pin "1") (pinfunction "1_1") (pintype "passive"))
      (node (ref "U13") (pin "6") (pinfunction "QG_6") (pintype "tri_state"))
      (node (ref "U14") (pin "7") (pinfunction "I7_7") (pintype "input"))
    )
    (net (code "127") (name "Net-(U13A-QH)") (class "Default")
      (node (ref "R18") (pin "1") (pinfunction "1_1") (pintype "passive"))
      (node (ref "U13") (pin "7") (pinfunction "QH_7") (pintype "tri_state"))
      (node (ref "U14") (pin "8") (pinfunction "I8_8") (pintype "input"))
    )
    (net (code "128") (name "OLAT") (class "Default")
      (node (ref "R21") (pin "1") (pinfunction "1_1") (pintype "passive"))
      (node (ref "U$1") (pin "PA8") (pinfunction "PA8_PA8") (pintype "bidirectional"))
      (node (ref "U11") (pin "12") (pinfunction "RCK_12") (pintype "input"))
      (node (ref "U13") (pin "12") (pinfunction "RCK_12") (pintype "input"))
    )
    (net (code "129") (name "SCK") (class "Default")
      (node (ref "JP2") (pin "3") (pinfunction "3_3") (pintype "passive"))
      (node (ref "R19") (pin "1") (pinfunction "1_1") (pintype "passive"))
      (node (ref "U$1") (pin "PB3") (pinfunction "PB3_PB3") (pintype "bidirectional"))
      (node (ref "U11") (pin "11") (pinfunction "SCK_11") (pintype "input"))
      (node (ref "U13") (pin "11") (pinfunction "SCK_11") (pintype "input"))
    )
    (net (code "130") (name "SCK2") (class "Default")
      (node (ref "U$1") (pin "PB10") (pinfunction "PB10_PB10") (pintype "bidirectional"))
      (node (ref "U1") (pin "7") (pinfunction "CLK_7") (pintype "input"))
      (node (ref "U2") (pin "7") (pinfunction "CLK_7") (pintype "input"))
    )
    (net (code "131") (name "SLNK1") (class "Default")
      (node (ref "SJ17") (pin "P$1") (pinfunction "1_P$1") (pintype "passive"))
      (node (ref "U11") (pin "9") (pinfunction "QH*_9") (pintype "tri_state"))
      (node (ref "U13") (pin "14") (pinfunction "SER_14") (pintype "input"))
    )
    (net (code "132") (name "SLNK2") (class "Default")
      (node (ref "SJ16") (pin "P$1") (pinfunction "1_P$1") (pintype "passive"))
      (node (ref "U13") (pin "9") (pinfunction "QH*_9") (pintype "tri_state"))
    )
    (net (code "133") (name "SLNK3") (class "Default")
      (node (ref "SJ19") (pin "P$1") (pinfunction "1_P$1") (pintype "passive"))
      (node (ref "U1") (pin "13") (pinfunction "QH_13") (pintype "output"))
      (node (ref "U2") (pin "1") (pinfunction "SER_1") (pintype "input"))
    )
    (net (code "134") (name "SRV1") (class "Default")
      (node (ref "JP5") (pin "2") (pinfunction "2_2") (pintype "passive"))
      (node (ref "R24") (pin "2") (pinfunction "2_2") (pintype "passive"))
      (node (ref "U$1") (pin "PC9") (pinfunction "PC9_PC9") (pintype "bidirectional"))
    )
    (net (code "135") (name "SRV2") (class "Default")
      (node (ref "JP5") (pin "1") (pinfunction "1_1") (pintype "passive"))
      (node (ref "R25") (pin "2") (pinfunction "2_2") (pintype "passive"))
      (node (ref "U$1") (pin "PC7") (pinfunction "PC7_PC7") (pintype "bidirectional"))
    )
    (net (code "136") (name "SRV3") (class "Default")
      (node (ref "JP6") (pin "2") (pinfunction "2_2") (pintype "passive"))
      (node (ref "R26") (pin "2") (pinfunction "2_2") (pintype "passive"))
      (node (ref "U$1") (pin "PC8") (pinfunction "PC8_PC8") (pintype "bidirectional"))
    )
    (net (code "137") (name "SRV4") (class "Default")
      (node (ref "JP6") (pin "1") (pinfunction "1_1") (pintype "passive"))
      (node (ref "R27") (pin "2") (pinfunction "2_2") (pintype "passive"))
      (node (ref "U$1") (pin "PC6") (pinfunction "PC6_PC6") (pintype "bidirectional"))
    )
    (net (code "138") (name "SRV5") (class "Default")
      (node (ref "JP7") (pin "2") (pinfunction "2_2") (pintype "passive"))
      (node (ref "R64") (pin "2") (pinfunction "2_2") (pintype "passive"))
      (node (ref "U$1") (pin "PF1-PH1") (pinfunction "PF1-PH1_PF1-PH1") (pintype "bidirectional"))
    )
    (net (code "139") (name "SRV6") (class "Default")
      (node (ref "JP7") (pin "1") (pinfunction "1_1") (pintype "passive"))
      (node (ref "R65") (pin "2") (pinfunction "2_2") (pintype "passive"))
      (node (ref "U$1") (pin "PA15") (pinfunction "PA15_PA15") (pintype "bidirectional"))
    )
    (net (code "140") (name "SRV7") (class "Default")
      (node (ref "JP8") (pin "2") (pinfunction "2_2") (pintype "passive"))
      (node (ref "R66") (pin "2") (pinfunction "2_2") (pintype "passive"))
      (node (ref "U$1") (pin "PC12") (pinfunction "PC12_PC12") (pintype "bidirectional"))
    )
    (net (code "141") (name "SRV8") (class "Default")
      (node (ref "JP8") (pin "1") (pinfunction "1_1") (pintype "passive"))
      (node (ref "R67") (pin "2") (pinfunction "2_2") (pintype "passive"))
      (node (ref "U$1") (pin "PD2") (pinfunction "PD2_PD2") (pintype "bidirectional"))
    )
    (net (code "142") (name "TDRV1") (class "Default")
      (node (ref "U$1") (pin "PB12") (pinfunction "PB12_PB12") (pintype "bidirectional"))
      (node (ref "U10") (pin "12") (pinfunction "+IN_12") (pintype "input"))
      (node (ref "U6") (pin "2") (pinfunction "I_2") (pintype "input"))
    )
    (net (code "143") (name "TDRV2") (class "Default")
      (node (ref "U$1") (pin "PB2") (pinfunction "PB2_PB2") (pintype "bidirectional"))
      (node (ref "U10") (pin "3") (pinfunction "+IN_3") (pintype "input"))
      (node (ref "U6") (pin "4") (pinfunction "I_4") (pintype "input"))
    )
    (net (code "144") (name "TDRV3") (class "Default")
      (node (ref "U$1") (pin "PB15") (pinfunction "PB15_PB15") (pintype "bidirectional"))
      (node (ref "U10") (pin "10") (pinfunction "+IN_10") (pintype "input"))
      (node (ref "U5") (pin "4") (pinfunction "I_4") (pintype "input"))
    )
    (net (code "145") (name "TDRV4") (class "Default")
      (node (ref "U$1") (pin "PB1") (pinfunction "PB1_PB1") (pintype "bidirectional"))
      (node (ref "U10") (pin "5") (pinfunction "+IN_5") (pintype "input"))
      (node (ref "U5") (pin "2") (pinfunction "I_2") (pintype "input"))
    )
    (net (code "146") (name "TDRV5") (class "Default")
      (node (ref "U$1") (pin "PA0") (pinfunction "PA0_PA0") (pintype "bidirectional"))
      (node (ref "U4") (pin "2") (pinfunction "I_2") (pintype "input"))
      (node (ref "U9") (pin "12") (pinfunction "+IN_12") (pintype "input"))
    )
    (net (code "147") (name "TDRV6") (class "Default")
      (node (ref "U$1") (pin "PA4") (pinfunction "PA4_PA4") (pintype "bidirectional"))
      (node (ref "U4") (pin "4") (pinfunction "I_4") (pintype "input"))
      (node (ref "U9") (pin "3") (pinfunction "+IN_3") (pintype "input"))
    )
    (net (code "148") (name "TDRV7") (class "Default")
      (node (ref "U$1") (pin "PC3") (pinfunction "PC3_PC3") (pintype "bidirectional"))
      (node (ref "U3") (pin "4") (pinfunction "I_4") (pintype "input"))
      (node (ref "U9") (pin "10") (pinfunction "+IN_10") (pintype "input"))
    )
    (net (code "149") (name "TDRV8") (class "Default")
      (node (ref "U$1") (pin "PC0") (pinfunction "PC0_PC0") (pintype "bidirectional"))
      (node (ref "U3") (pin "2") (pinfunction "I_2") (pintype "input"))
      (node (ref "U9") (pin "5") (pinfunction "+IN_5") (pintype "input"))
    )
    (net (code "150") (name "V+") (class "Default")
      (node (ref "C1") (pin "1") (pinfunction "1_1") (pintype "passive"))
      (node (ref "C2") (pin "+") (pinfunction "+_+") (pintype "passive"))
      (node (ref "L1") (pin "1") (pinfunction "1_1") (pintype "passive"))
      (node (ref "U$1") (pin "E5V") (pinfunction "E5V_E5V") (pintype "power_in"))
      (node (ref "U8") (pin "3") (pinfunction "FB_3") (pintype "bidirectional"))
      (node (ref "U8B") (pin "1") (pinfunction "FB_1") (pintype "input"))
    )
    (net (code "151") (name "unconnected-(H1-MOUNT-PadB3,3)") (class "Default")
      (node (ref "H1") (pin "B3,3") (pinfunction "MOUNT_B3,3") (pintype "passive"))
    )
    (net (code "152") (name "unconnected-(H2-MOUNT-PadB3,3)") (class "Default")
      (node (ref "H2") (pin "B3,3") (pinfunction "MOUNT_B3,3") (pintype "passive"))
    )
    (net (code "153") (name "unconnected-(H3-MOUNT-PadB3,3)") (class "Default")
      (node (ref "H3") (pin "B3,3") (pinfunction "MOUNT_B3,3") (pintype "passive"))
    )
    (net (code "154") (name "unconnected-(H4-MOUNT-PadB3,3)") (class "Default")
      (node (ref "H4") (pin "B3,3") (pinfunction "MOUNT_B3,3") (pintype "passive"))
    )
    (net (code "155") (name "unconnected-(U$1-PadBOOT0)") (class "Default")
      (node (ref "U$1") (pin "BOOT0") (pinfunction "BOOT0_BOOT0") (pintype "bidirectional"))
    )
    (net (code "156") (name "unconnected-(U$1-PadIOREF2)") (class "Default")
      (node (ref "U$1") (pin "IOREF2") (pinfunction "IOREF2_IOREF2") (pintype "input"))
    )
    (net (code "157") (name "unconnected-(U$1-PadNC1-PF7)") (class "Default")
      (node (ref "U$1") (pin "NC1-PF7") (pinfunction "NC1-PF7_NC1-PF7") (pintype "bidirectional"))
    )
    (net (code "158") (name "unconnected-(U$1-PadNC2-PF6)") (class "Default")
      (node (ref "U$1") (pin "NC2-PF6") (pinfunction "NC2-PF6_NC2-PF6") (pintype "bidirectional"))
    )
    (net (code "159") (name "unconnected-(U$1-PadNC3)") (class "Default")
      (node (ref "U$1") (pin "NC3") (pinfunction "NC3_NC3") (pintype "no_connect"))
    )
    (net (code "160") (name "unconnected-(U$1-PadNC4)") (class "Default")
      (node (ref "U$1") (pin "NC4") (pinfunction "NC4_NC4") (pintype "no_connect"))
    )
    (net (code "161") (name "unconnected-(U$1-PadNC5-PD8)") (class "Default")
      (node (ref "U$1") (pin "NC5-PD8") (pinfunction "NC5-PD8_NC5-PD8") (pintype "bidirectional"))
    )
    (net (code "162") (name "unconnected-(U$1-PadNC6-PB11)") (class "Default")
      (node (ref "U$1") (pin "NC6-PB11") (pinfunction "NC6-PB11_NC6-PB11") (pintype "no_connect"))
    )
    (net (code "163") (name "unconnected-(U$1-PadNC7-PF5)") (class "Default")
      (node (ref "U$1") (pin "NC7-PF5") (pinfunction "NC7-PF5_NC7-PF5") (pintype "bidirectional"))
    )
    (net (code "164") (name "unconnected-(U$1-PadNC8-PF4)") (class "Default")
      (node (ref "U$1") (pin "NC8-PF4") (pinfunction "NC8-PF4_NC8-PF4") (pintype "bidirectional"))
    )
    (net (code "165") (name "unconnected-(U$1-PadNRESET)") (class "Default")
      (node (ref "U$1") (pin "NRESET") (pinfunction "NRESET_NRESET") (pintype "input"))
    )
    (net (code "166") (name "unconnected-(U$1-PadPA1)") (class "Default")
      (node (ref "U$1") (pin "PA1") (pinfunction "PA1_PA1") (pintype "bidirectional"))
    )
    (net (code "167") (name "unconnected-(U$1-PadPA2)") (class "Default")
      (node (ref "U$1") (pin "PA2") (pinfunction "PA2_PA2") (pintype "bidirectional"))
    )
    (net (code "168") (name "unconnected-(U$1-PadPA3)") (class "Default")
      (node (ref "U$1") (pin "PA3") (pinfunction "PA3_PA3") (pintype "bidirectional"))
    )
    (net (code "169") (name "unconnected-(U$1-PadPA5)") (class "Default")
      (node (ref "U$1") (pin "PA5") (pinfunction "PA5_PA5") (pintype "bidirectional"))
    )
    (net (code "170") (name "unconnected-(U$1-PadPA7)") (class "Default")
      (node (ref "U$1") (pin "PA7") (pinfunction "PA7_PA7") (pintype "bidirectional"))
    )
    (net (code "171") (name "unconnected-(U$1-PadPA9)") (class "Default")
      (node (ref "U$1") (pin "PA9") (pinfunction "PA9_PA9") (pintype "bidirectional"))
    )
    (net (code "172") (name "unconnected-(U$1-PadPA10)") (class "Default")
      (node (ref "U$1") (pin "PA10") (pinfunction "PA10_PA10") (pintype "bidirectional"))
    )
    (net (code "173") (name "unconnected-(U$1-PadPA11)") (class "Default")
      (node (ref "U$1") (pin "PA11") (pinfunction "PA11_PA11") (pintype "bidirectional"))
    )
    (net (code "174") (name "unconnected-(U$1-PadPA12)") (class "Default")
      (node (ref "U$1") (pin "PA12") (pinfunction "PA12_PA12") (pintype "bidirectional"))
    )
    (net (code "175") (name "unconnected-(U$1-PadPA13)") (class "Default")
      (node (ref "U$1") (pin "PA13") (pinfunction "PA13_PA13") (pintype "bidirectional"))
    )
    (net (code "176") (name "unconnected-(U$1-PadPA14)") (class "Default")
      (node (ref "U$1") (pin "PA14") (pinfunction "PA14_PA14") (pintype "bidirectional"))
    )
    (net (code "177") (name "unconnected-(U$1-PadPB0)") (class "Default")
      (node (ref "U$1") (pin "PB0") (pinfunction "PB0_PB0") (pintype "bidirectional"))
    )
    (net (code "178") (name "unconnected-(U$1-PadPB13)") (class "Default")
      (node (ref "U$1") (pin "PB13") (pinfunction "PB13_PB13") (pintype "bidirectional"))
    )
    (net (code "179") (name "unconnected-(U$1-PadPC1)") (class "Default")
      (node (ref "U$1") (pin "PC1") (pinfunction "PC1_PC1") (pintype "bidirectional"))
    )
    (net (code "180") (name "unconnected-(U$1-PadPC4)") (class "Default")
      (node (ref "U$1") (pin "PC4") (pinfunction "PC4_PC4") (pintype "bidirectional"))
    )
    (net (code "181") (name "unconnected-(U$1-PadPC5)") (class "Default")
      (node (ref "U$1") (pin "PC5") (pinfunction "PC5_PC5") (pintype "bidirectional"))
    )
    (net (code "182") (name "unconnected-(U$1-PadPC13)") (class "Default")
      (node (ref "U$1") (pin "PC13") (pinfunction "PC13_PC13") (pintype "bidirectional"))
    )
    (net (code "183") (name "unconnected-(U$1-PadPC14)") (class "Default")
      (node (ref "U$1") (pin "PC14") (pinfunction "PC14_PC14") (pintype "bidirectional"))
    )
    (net (code "184") (name "unconnected-(U$1-PadPC15)") (class "Default")
      (node (ref "U$1") (pin "PC15") (pinfunction "PC15_PC15") (pintype "bidirectional"))
    )
    (net (code "185") (name "unconnected-(U$1-PadPF0-PH0)") (class "Default")
      (node (ref "U$1") (pin "PF0-PH0") (pinfunction "PF0-PH0_PF0-PH0") (pintype "bidirectional"))
    )
  )
)
